# main.net
KiCad netlist of a schematic drawn in EAGLE
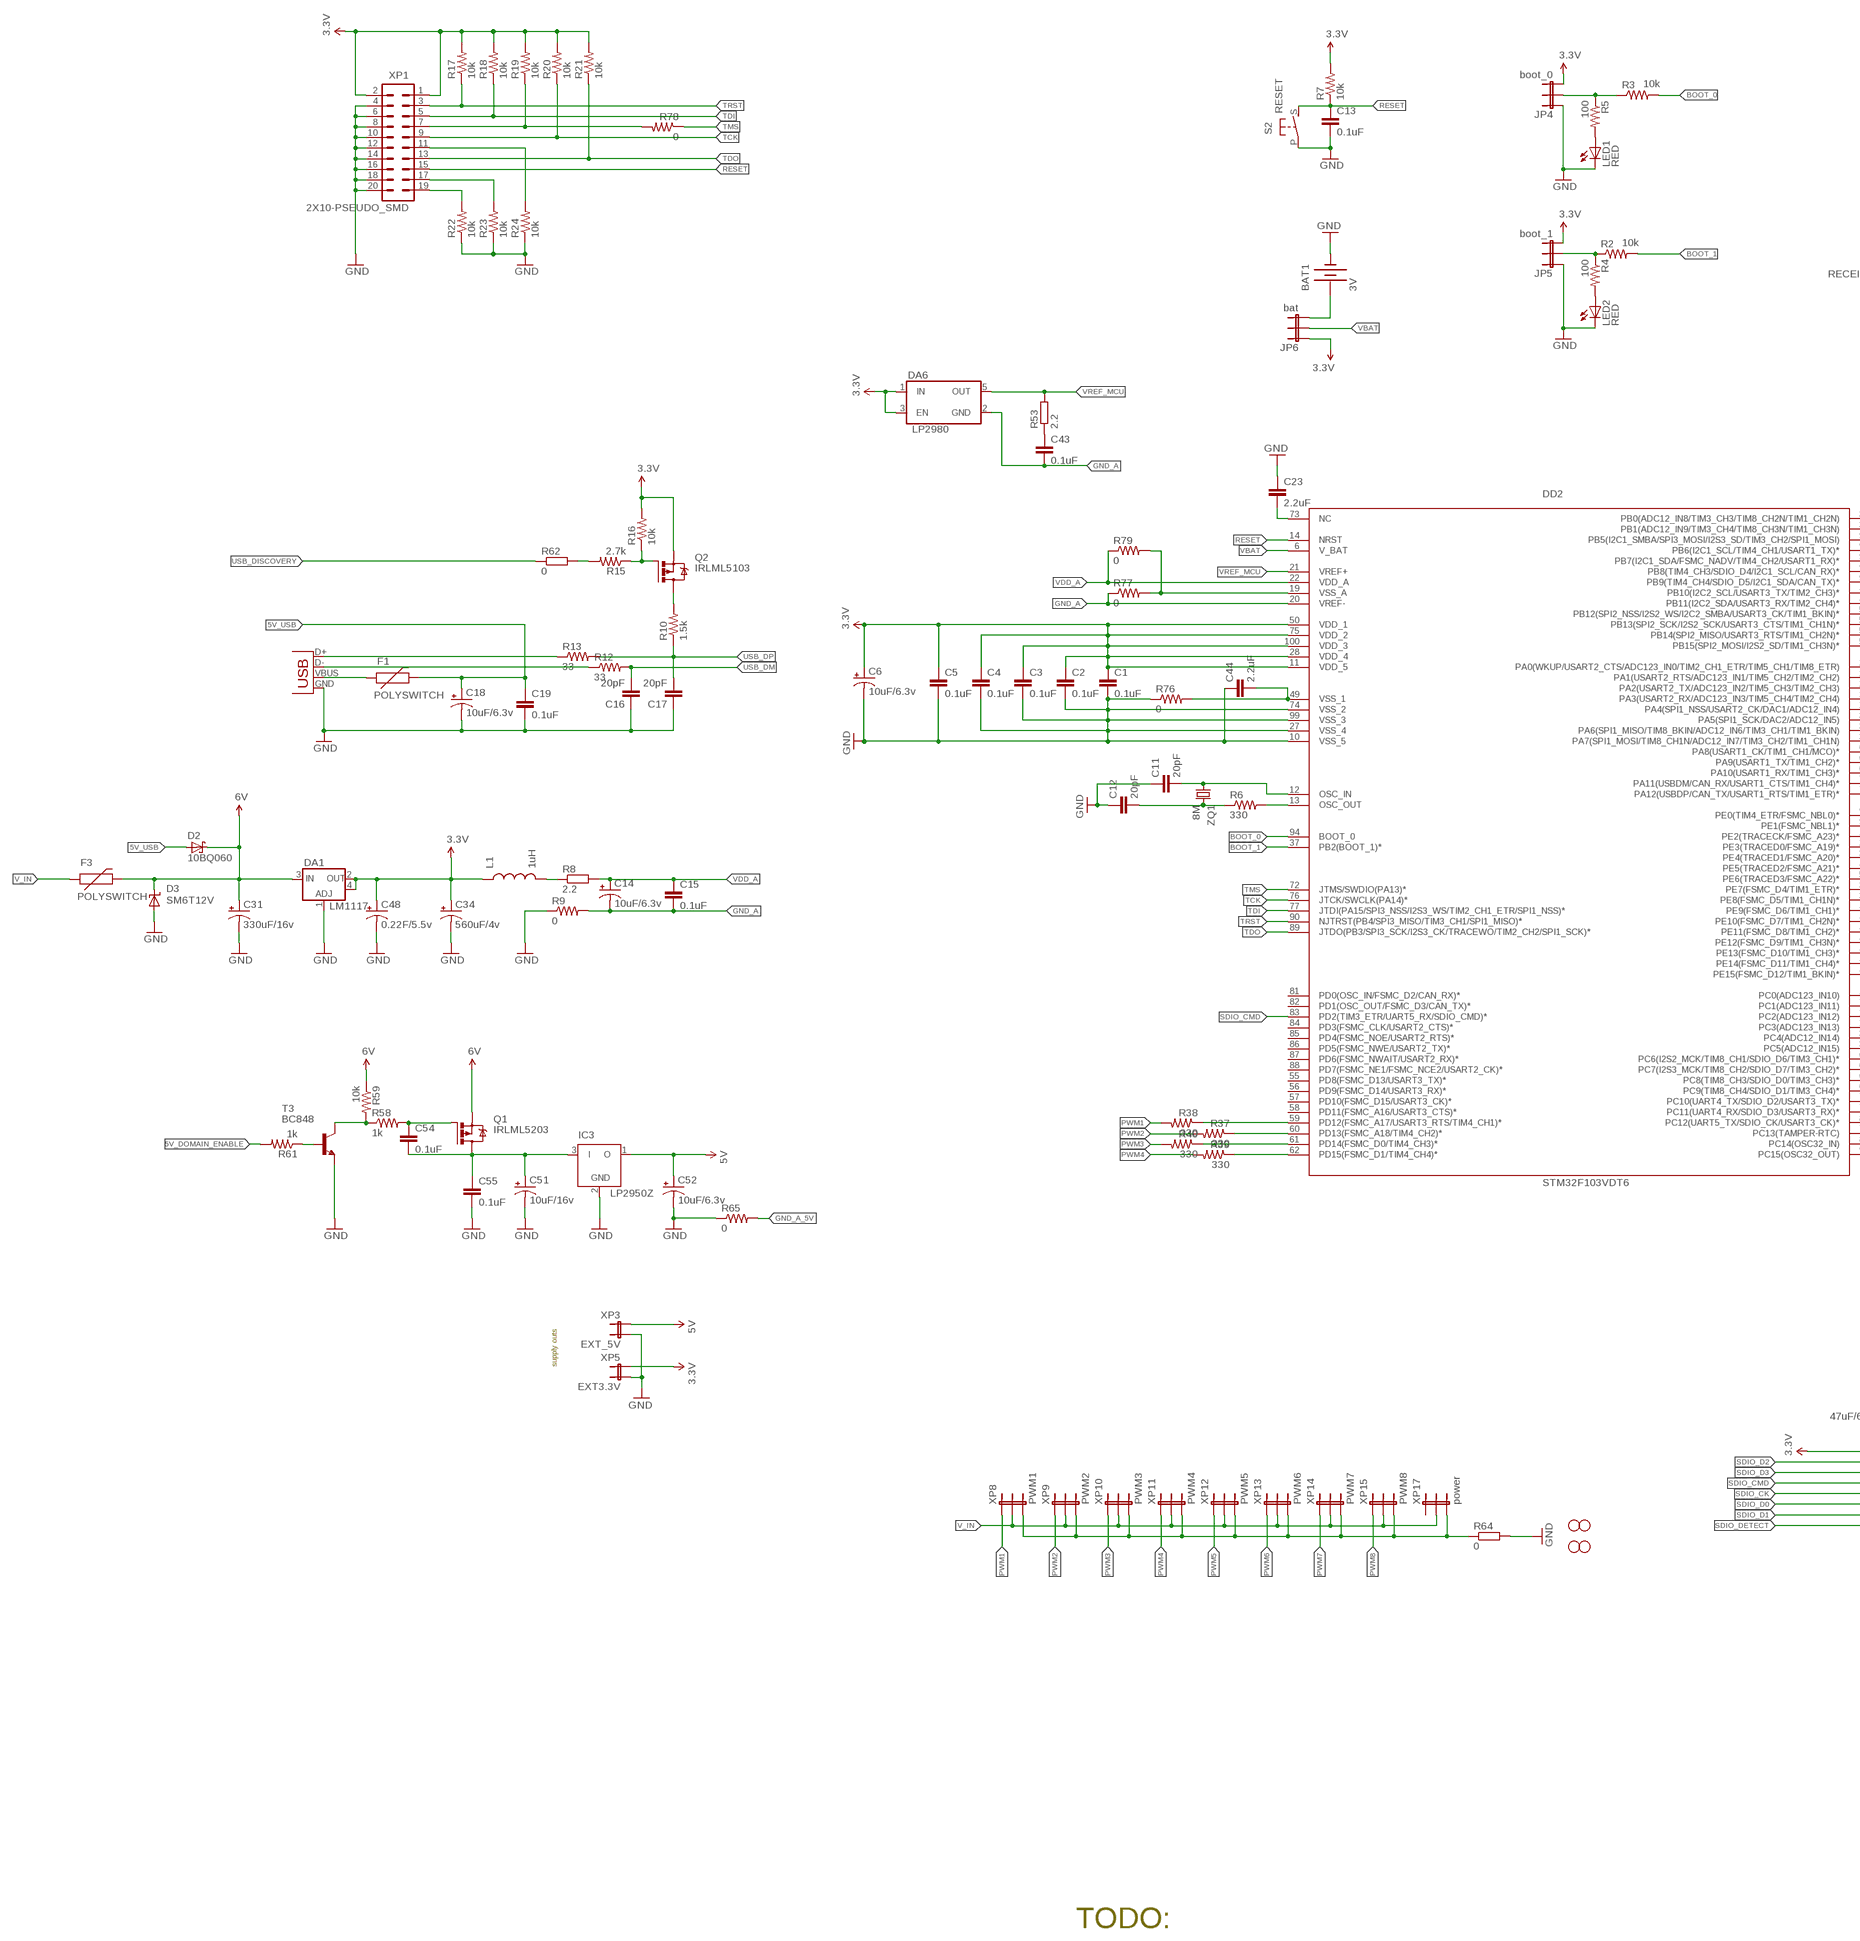
[diagram p0: schematic, sheet 1, part 1 of 3]
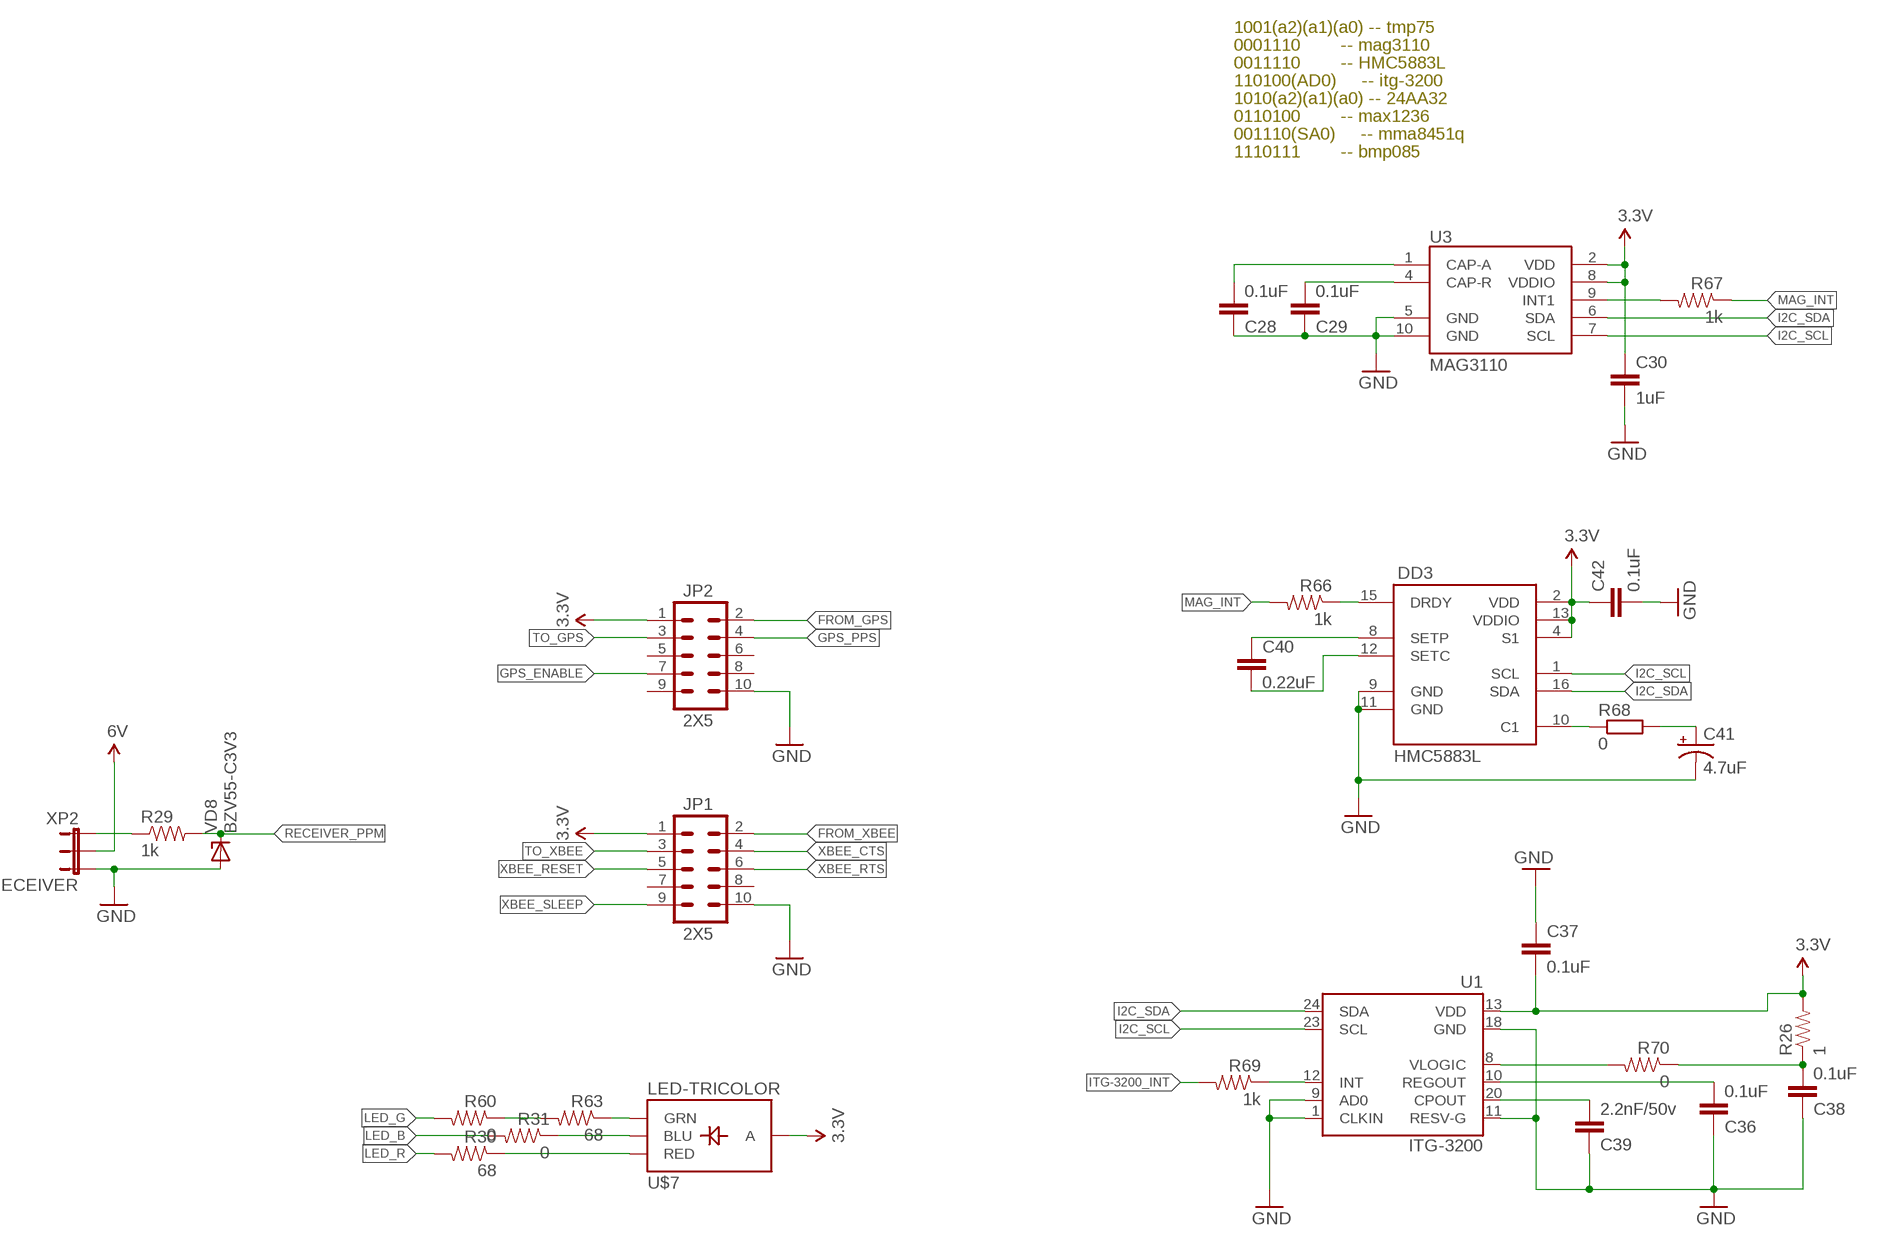
[diagram p1: schematic, sheet 1, part 2 of 3]
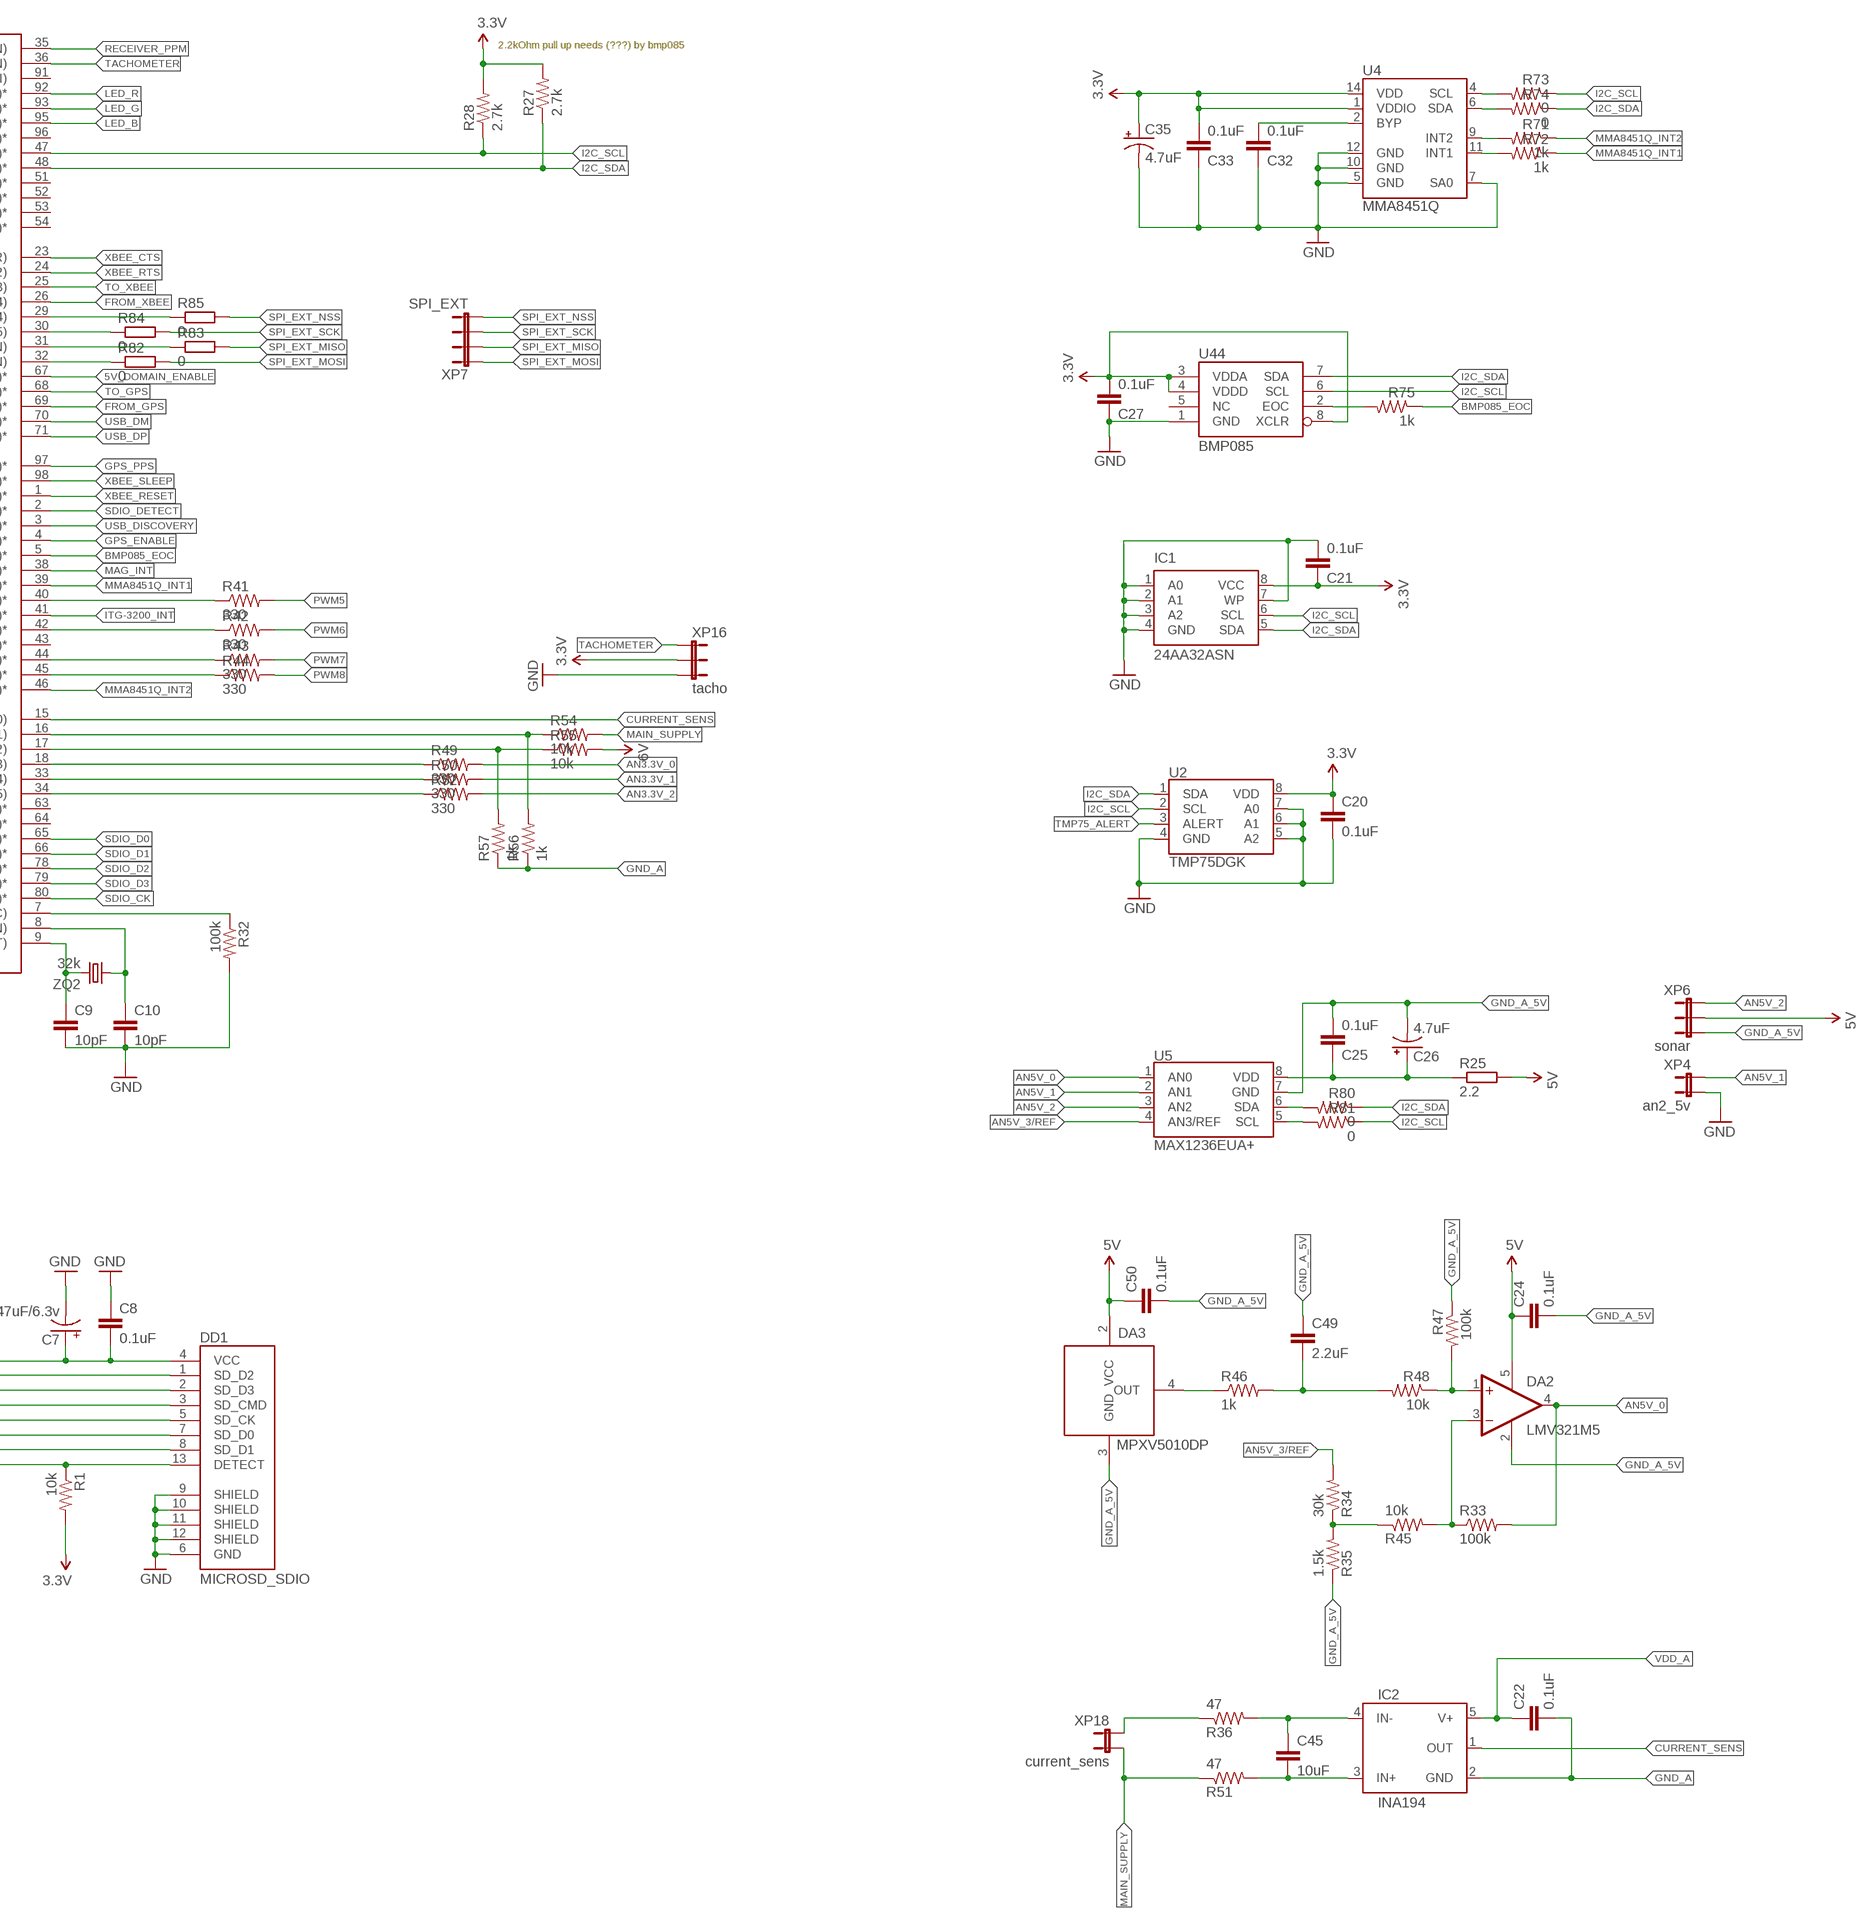
[diagram p2: schematic, sheet 1, part 3 of 3]

(export (version "E")
  (design (tool "Eeschema 10.0.6"))
  (components
    (comp (ref "BAT1")
      (value "3V")
      (footprint "eagle-import:BATTCOM_20MM_PTH")
      (libsource (lib "eagle-import") (part "BATTERY20PTH"))
    )
    (comp (ref "C1")
      (value "0.1uF")
      (footprint "eagle-import:0805")
      (libsource (lib "eagle-import") (part "CAP0805"))
    )
    (comp (ref "C2")
      (value "0.1uF")
      (footprint "eagle-import:0805")
      (libsource (lib "eagle-import") (part "CAP0805"))
    )
    (comp (ref "C3")
      (value "0.1uF")
      (footprint "eagle-import:0805")
      (libsource (lib "eagle-import") (part "CAP0805"))
    )
    (comp (ref "C4")
      (value "0.1uF")
      (footprint "eagle-import:0805")
      (libsource (lib "eagle-import") (part "CAP0805"))
    )
    (comp (ref "C5")
      (value "0.1uF")
      (footprint "eagle-import:0805")
      (libsource (lib "eagle-import") (part "CAP0805"))
    )
    (comp (ref "C6")
      (value "10uF/6.3v")
      (footprint "eagle-import:EIA3216-KIT")
      (libsource (lib "eagle-import") (part "CAP_POL1206-KIT"))
    )
    (comp (ref "C7")
      (value "47uF/6.3v")
      (footprint "eagle-import:EIA3216-KIT")
      (libsource (lib "eagle-import") (part "CAP_POL1206-KIT"))
    )
    (comp (ref "C8")
      (value "0.1uF")
      (footprint "eagle-import:0805")
      (libsource (lib "eagle-import") (part "CAP0805"))
    )
    (comp (ref "C9")
      (value "10pF")
      (footprint "eagle-import:0805")
      (libsource (lib "eagle-import") (part "CAP0805"))
    )
    (comp (ref "C10")
      (value "10pF")
      (footprint "eagle-import:0805")
      (libsource (lib "eagle-import") (part "CAP0805"))
    )
    (comp (ref "C11")
      (value "20pF")
      (footprint "eagle-import:0805")
      (libsource (lib "eagle-import") (part "CAP0805"))
    )
    (comp (ref "C12")
      (value "20pF")
      (footprint "eagle-import:0805")
      (libsource (lib "eagle-import") (part "CAP0805"))
    )
    (comp (ref "C13")
      (value "0.1uF")
      (footprint "eagle-import:0805")
      (libsource (lib "eagle-import") (part "CAP0805"))
    )
    (comp (ref "C14")
      (value "10uF/6.3v")
      (footprint "eagle-import:EIA3216-KIT")
      (libsource (lib "eagle-import") (part "CAP_POL1206-KIT"))
    )
    (comp (ref "C15")
      (value "0.1uF")
      (footprint "eagle-import:0805")
      (libsource (lib "eagle-import") (part "CAP0805"))
    )
    (comp (ref "C16")
      (value "20pF")
      (footprint "eagle-import:0805")
      (libsource (lib "eagle-import") (part "CAP0805"))
    )
    (comp (ref "C17")
      (value "20pF")
      (footprint "eagle-import:0805")
      (libsource (lib "eagle-import") (part "CAP0805"))
    )
    (comp (ref "C18")
      (value "10uF/6.3v")
      (footprint "eagle-import:EIA3216-KIT")
      (libsource (lib "eagle-import") (part "CAP_POL1206-KIT"))
    )
    (comp (ref "C19")
      (value "0.1uF")
      (footprint "eagle-import:0805")
      (libsource (lib "eagle-import") (part "CAP0805"))
    )
    (comp (ref "C20")
      (value "0.1uF")
      (footprint "eagle-import:0805")
      (libsource (lib "eagle-import") (part "CAP0805"))
    )
    (comp (ref "C21")
      (value "0.1uF")
      (footprint "eagle-import:0805")
      (libsource (lib "eagle-import") (part "CAP0805"))
    )
    (comp (ref "C22")
      (value "0.1uF")
      (footprint "eagle-import:0805")
      (libsource (lib "eagle-import") (part "CAP0805"))
    )
    (comp (ref "C23")
      (value "2.2uF")
      (footprint "eagle-import:0805")
      (libsource (lib "eagle-import") (part "CAP0805"))
    )
    (comp (ref "C24")
      (value "0.1uF")
      (footprint "eagle-import:0805")
      (libsource (lib "eagle-import") (part "CAP0805"))
    )
    (comp (ref "C25")
      (value "0.1uF")
      (footprint "eagle-import:0805")
      (libsource (lib "eagle-import") (part "CAP0805"))
    )
    (comp (ref "C26")
      (value "4.7uF")
      (footprint "eagle-import:EIA3216-KIT")
      (libsource (lib "eagle-import") (part "CAP_POL1206-KIT"))
    )
    (comp (ref "C27")
      (value "0.1uF")
      (footprint "eagle-import:0805")
      (libsource (lib "eagle-import") (part "CAP0805"))
    )
    (comp (ref "C28")
      (value "0.1uF")
      (footprint "eagle-import:0805")
      (libsource (lib "eagle-import") (part "CAP0805"))
    )
    (comp (ref "C29")
      (value "0.1uF")
      (footprint "eagle-import:0805")
      (libsource (lib "eagle-import") (part "CAP0805"))
    )
    (comp (ref "C30")
      (value "1uF")
      (footprint "eagle-import:0805")
      (libsource (lib "eagle-import") (part "CAP0805"))
    )
    (comp (ref "C31")
      (value "330uF/16v")
      (footprint "eagle-import:CPOL-RADIAL-1000UF-25V")
      (libsource (lib "eagle-import") (part "CAP_POLPTH4"))
    )
    (comp (ref "C32")
      (value "0.1uF")
      (footprint "eagle-import:0805")
      (libsource (lib "eagle-import") (part "CAP0805"))
    )
    (comp (ref "C33")
      (value "0.1uF")
      (footprint "eagle-import:0805")
      (libsource (lib "eagle-import") (part "CAP0805"))
    )
    (comp (ref "C34")
      (value "560uF/4v")
      (footprint "eagle-import:E3,5-8")
      (libsource (lib "eagle-import") (part "CPOL-USE3.5-8"))
    )
    (comp (ref "C35")
      (value "4.7uF")
      (footprint "eagle-import:EIA3216-KIT")
      (libsource (lib "eagle-import") (part "CAP_POL1206-KIT"))
    )
    (comp (ref "C36")
      (value "0.1uF")
      (footprint "eagle-import:0805")
      (libsource (lib "eagle-import") (part "CAP0805"))
    )
    (comp (ref "C37")
      (value "0.1uF")
      (footprint "eagle-import:0805")
      (libsource (lib "eagle-import") (part "CAP0805"))
    )
    (comp (ref "C38")
      (value "0.1uF")
      (footprint "eagle-import:0805")
      (libsource (lib "eagle-import") (part "CAP0805"))
    )
    (comp (ref "C39")
      (value "2.2nF/50v")
      (footprint "eagle-import:0805")
      (libsource (lib "eagle-import") (part "CAP0805"))
    )
    (comp (ref "C40")
      (value "0.22uF")
      (footprint "eagle-import:0805")
      (libsource (lib "eagle-import") (part "CAP0805"))
    )
    (comp (ref "C41")
      (value "4.7uF")
      (footprint "eagle-import:EIA3216-KIT")
      (libsource (lib "eagle-import") (part "CAP_POL1206-KIT"))
    )
    (comp (ref "C42")
      (value "0.1uF")
      (footprint "eagle-import:0805")
      (libsource (lib "eagle-import") (part "CAP0805"))
    )
    (comp (ref "C43")
      (value "0.1uF")
      (footprint "eagle-import:0805")
      (libsource (lib "eagle-import") (part "CAP0805"))
    )
    (comp (ref "C44")
      (value "2.2uF")
      (footprint "eagle-import:0805")
      (libsource (lib "eagle-import") (part "CAP0805"))
    )
    (comp (ref "C45")
      (value "10uF")
      (footprint "eagle-import:1206")
      (libsource (lib "eagle-import") (part "CAP1206"))
    )
    (comp (ref "C48")
      (value "0.22F/5.5v")
      (footprint "eagle-import:CAP-IONISTOR-5MM")
      (libsource (lib "eagle-import") (part "CAP_POLIONISTOR"))
    )
    (comp (ref "C49")
      (value "2.2uF")
      (footprint "eagle-import:C1206")
      (libsource (lib "eagle-import") (part "C-EUC1206"))
    )
    (comp (ref "C50")
      (value "0.1uF")
      (footprint "eagle-import:0805")
      (libsource (lib "eagle-import") (part "CAP0805"))
    )
    (comp (ref "C51")
      (value "10uF/16v")
      (footprint "eagle-import:EIA3216-KIT")
      (libsource (lib "eagle-import") (part "CAP_POL1206-KIT"))
    )
    (comp (ref "C52")
      (value "10uF/6.3v")
      (footprint "eagle-import:EIA3216-KIT")
      (libsource (lib "eagle-import") (part "CAP_POL1206-KIT"))
    )
    (comp (ref "C54")
      (value "0.1uF")
      (footprint "eagle-import:0805")
      (libsource (lib "eagle-import") (part "CAP0805"))
    )
    (comp (ref "C55")
      (value "0.1uF")
      (footprint "eagle-import:0805")
      (libsource (lib "eagle-import") (part "CAP0805"))
    )
    (comp (ref "D2")
      (value "10BQ060")
      (footprint "eagle-import:SMB")
      (libsource (lib "eagle-import") (part "SCHOTTKY-DIODESMD"))
    )
    (comp (ref "D3")
      (value "SM6T12V")
      (footprint "eagle-import:SMBJ")
      (libsource (lib "eagle-import") (part "SUPPRESSOR-SMBJ"))
    )
    (comp (ref "DA1")
      (value "LM1117")
      (footprint "eagle-import:SOT223")
      (libsource (lib "eagle-import") (part "LM1117"))
    )
    (comp (ref "DA2")
      (value "LMV321M5")
      (footprint "eagle-import:SOT23-5")
      (libsource (lib "eagle-import") (part "LMV321?M5"))
    )
    (comp (ref "DA3")
      (value "MPXV5010DP")
      (footprint "eagle-import:482")
      (libsource (lib "eagle-import") (part "MPXV5010DP"))
    )
    (comp (ref "DA6")
      (value "LP2980")
      (footprint "eagle-import:SOT23-5")
      (libsource (lib "eagle-import") (part "LP2980"))
    )
    (comp (ref "DD1")
      (value "MICROSD_SDIO")
      (footprint "eagle-import:MICROSD")
      (libsource (lib "eagle-import") (part "MICROSD_SDIO"))
    )
    (comp (ref "DD2")
      (value "STM32F103VDT6")
      (footprint "eagle-import:TQFP100")
      (libsource (lib "eagle-import") (part "STM32F103VDT6"))
    )
    (comp (ref "DD3")
      (value "HMC5883L")
      (footprint "eagle-import:16LPCC")
      (libsource (lib "eagle-import") (part "HMC5883L"))
    )
    (comp (ref "F1")
      (value "POLYSWITCH")
      (footprint "eagle-import:1812")
      (libsource (lib "eagle-import") (part "POLYSWITCH"))
    )
    (comp (ref "F3")
      (value "POLYSWITCH")
      (footprint "eagle-import:1812")
      (libsource (lib "eagle-import") (part "POLYSWITCH"))
    )
    (comp (ref "IC1")
      (value "24AA32ASN")
      (footprint "eagle-import:SO-08")
      (fields (field (name "MF") "MICROCHIP") (field (name "MPN") "24AA32A-I/SN"))
      (libsource (lib "eagle-import") (part "24SNAA32A"))
    )
    (comp (ref "IC2")
      (value "INA194")
      (footprint "eagle-import:SOT23-5")
      (fields (field (name "MF") "TEXAS INSTRUMENTS") (field (name "MPN") "INA168NA/250"))
      (libsource (lib "eagle-import") (part "INA194"))
    )
    (comp (ref "IC3")
      (value "LP2950Z")
      (footprint "eagle-import:TO92")
      (libsource (lib "eagle-import") (part "LP2950Z"))
    )
    (comp (ref "JP1")
      (value "2X5")
      (footprint "eagle-import:2X5-PSEUDOSMD")
      (libsource (lib "eagle-import") (part "2X5"))
    )
    (comp (ref "JP2")
      (value "2X5")
      (footprint "eagle-import:2X5-PSEUDOSMD")
      (libsource (lib "eagle-import") (part "2X5"))
    )
    (comp (ref "JP3")
      (value "STAND-OFFTIGHT")
      (footprint "eagle-import:STAND-OFF-TIGHT")
      (libsource (lib "eagle-import") (part "STAND-OFFTIGHT"))
    )
    (comp (ref "JP4")
      (value "boot_0")
      (footprint "eagle-import:1X03")
      (libsource (lib "eagle-import") (part "JUMPER-3PTH"))
    )
    (comp (ref "JP5")
      (value "boot_1")
      (footprint "eagle-import:1X03")
      (libsource (lib "eagle-import") (part "JUMPER-3PTH"))
    )
    (comp (ref "JP6")
      (value "bat")
      (footprint "eagle-import:1X03")
      (libsource (lib "eagle-import") (part "JUMPER-3PTH"))
    )
    (comp (ref "JP7")
      (value "STAND-OFFTIGHT")
      (footprint "eagle-import:STAND-OFF-TIGHT")
      (libsource (lib "eagle-import") (part "STAND-OFFTIGHT"))
    )
    (comp (ref "JP8")
      (value "STAND-OFFTIGHT")
      (footprint "eagle-import:STAND-OFF-TIGHT")
      (libsource (lib "eagle-import") (part "STAND-OFFTIGHT"))
    )
    (comp (ref "JP9")
      (value "STAND-OFFTIGHT")
      (footprint "eagle-import:STAND-OFF-TIGHT")
      (libsource (lib "eagle-import") (part "STAND-OFFTIGHT"))
    )
    (comp (ref "L1")
      (value "1uH")
      (footprint "eagle-import:1210")
      (libsource (lib "eagle-import") (part "INDUCTOR1210"))
    )
    (comp (ref "LED1")
      (value "RED")
      (footprint "eagle-import:LED-0805")
      (libsource (lib "eagle-import") (part "LED0805"))
    )
    (comp (ref "LED2")
      (value "RED")
      (footprint "eagle-import:LED-0805")
      (libsource (lib "eagle-import") (part "LED0805"))
    )
    (comp (ref "Q1")
      (value "IRLML5203")
      (footprint "eagle-import:MICRO3")
      (libsource (lib "eagle-import") (part "IRLML5203"))
    )
    (comp (ref "Q2")
      (value "IRLML5103")
      (footprint "eagle-import:MICRO3")
      (libsource (lib "eagle-import") (part "IRLML5203"))
    )
    (comp (ref "R1")
      (value "10k")
      (footprint "eagle-import:0805")
      (libsource (lib "eagle-import") (part "RESISTOR0805-RES"))
    )
    (comp (ref "R2")
      (value "10k")
      (footprint "eagle-import:0805")
      (libsource (lib "eagle-import") (part "RESISTOR0805-RES"))
    )
    (comp (ref "R3")
      (value "10k")
      (footprint "eagle-import:0805")
      (libsource (lib "eagle-import") (part "RESISTOR0805-RES"))
    )
    (comp (ref "R4")
      (value "100")
      (footprint "eagle-import:0805")
      (libsource (lib "eagle-import") (part "RESISTOR0805-RES"))
    )
    (comp (ref "R5")
      (value "100")
      (footprint "eagle-import:0805")
      (libsource (lib "eagle-import") (part "RESISTOR0805-RES"))
    )
    (comp (ref "R6")
      (value "330")
      (footprint "eagle-import:0805")
      (libsource (lib "eagle-import") (part "RESISTOR0805-RES"))
    )
    (comp (ref "R7")
      (value "10k")
      (footprint "eagle-import:0805")
      (libsource (lib "eagle-import") (part "RESISTOR0805-RES"))
    )
    (comp (ref "R8")
      (value "2.2")
      (footprint "eagle-import:R1206")
      (libsource (lib "eagle-import") (part "R-EU_R1206"))
    )
    (comp (ref "R9")
      (value "0")
      (footprint "eagle-import:0805")
      (libsource (lib "eagle-import") (part "RESISTOR0805-RES"))
    )
    (comp (ref "R10")
      (value "1.5k")
      (footprint "eagle-import:0805")
      (libsource (lib "eagle-import") (part "RESISTOR0805-RES"))
    )
    (comp (ref "R12")
      (value "33")
      (footprint "eagle-import:0805")
      (libsource (lib "eagle-import") (part "RESISTOR0805-RES"))
    )
    (comp (ref "R13")
      (value "33")
      (footprint "eagle-import:0805")
      (libsource (lib "eagle-import") (part "RESISTOR0805-RES"))
    )
    (comp (ref "R15")
      (value "2.7k")
      (footprint "eagle-import:0805")
      (libsource (lib "eagle-import") (part "RESISTOR0805-RES"))
    )
    (comp (ref "R16")
      (value "10k")
      (footprint "eagle-import:0805")
      (libsource (lib "eagle-import") (part "RESISTOR0805-RES"))
    )
    (comp (ref "R17")
      (value "10k")
      (footprint "eagle-import:0805")
      (libsource (lib "eagle-import") (part "RESISTOR0805-RES"))
    )
    (comp (ref "R18")
      (value "10k")
      (footprint "eagle-import:0805")
      (libsource (lib "eagle-import") (part "RESISTOR0805-RES"))
    )
    (comp (ref "R19")
      (value "10k")
      (footprint "eagle-import:0805")
      (libsource (lib "eagle-import") (part "RESISTOR0805-RES"))
    )
    (comp (ref "R20")
      (value "10k")
      (footprint "eagle-import:0805")
      (libsource (lib "eagle-import") (part "RESISTOR0805-RES"))
    )
    (comp (ref "R21")
      (value "10k")
      (footprint "eagle-import:0805")
      (libsource (lib "eagle-import") (part "RESISTOR0805-RES"))
    )
    (comp (ref "R22")
      (value "10k")
      (footprint "eagle-import:0805")
      (libsource (lib "eagle-import") (part "RESISTOR0805-RES"))
    )
    (comp (ref "R23")
      (value "10k")
      (footprint "eagle-import:0805")
      (libsource (lib "eagle-import") (part "RESISTOR0805-RES"))
    )
    (comp (ref "R24")
      (value "10k")
      (footprint "eagle-import:0805")
      (libsource (lib "eagle-import") (part "RESISTOR0805-RES"))
    )
    (comp (ref "R25")
      (value "2.2")
      (footprint "eagle-import:R1206")
      (libsource (lib "eagle-import") (part "barthess_RESISTOR1206"))
    )
    (comp (ref "R26")
      (value "1")
      (footprint "eagle-import:0805")
      (libsource (lib "eagle-import") (part "RESISTOR0805-RES"))
    )
    (comp (ref "R27")
      (value "2.7k")
      (footprint "eagle-import:0805")
      (libsource (lib "eagle-import") (part "RESISTOR0805-RES"))
    )
    (comp (ref "R28")
      (value "2.7k")
      (footprint "eagle-import:0805")
      (libsource (lib "eagle-import") (part "RESISTOR0805-RES"))
    )
    (comp (ref "R29")
      (value "1k")
      (footprint "eagle-import:0805")
      (libsource (lib "eagle-import") (part "RESISTOR0805-RES"))
    )
    (comp (ref "R30")
      (value "68")
      (footprint "eagle-import:0805")
      (libsource (lib "eagle-import") (part "RESISTOR0805-RES"))
    )
    (comp (ref "R31")
      (value "0")
      (footprint "eagle-import:0805")
      (libsource (lib "eagle-import") (part "RESISTOR0805-RES"))
    )
    (comp (ref "R32")
      (value "100k")
      (footprint "eagle-import:0805")
      (libsource (lib "eagle-import") (part "RESISTOR0805-RES"))
    )
    (comp (ref "R33")
      (value "100k")
      (footprint "eagle-import:0805")
      (libsource (lib "eagle-import") (part "RESISTOR0805-RES"))
    )
    (comp (ref "R34")
      (value "30k")
      (footprint "eagle-import:0805")
      (libsource (lib "eagle-import") (part "RESISTOR0805-RES"))
    )
    (comp (ref "R35")
      (value "1.5k")
      (footprint "eagle-import:0805")
      (libsource (lib "eagle-import") (part "RESISTOR0805-RES"))
    )
    (comp (ref "R36")
      (value "47")
      (footprint "eagle-import:0805")
      (libsource (lib "eagle-import") (part "RESISTOR0805-RES"))
    )
    (comp (ref "R37")
      (value "330")
      (footprint "eagle-import:0805")
      (libsource (lib "eagle-import") (part "RESISTOR0805-RES"))
    )
    (comp (ref "R38")
      (value "330")
      (footprint "eagle-import:0805")
      (libsource (lib "eagle-import") (part "RESISTOR0805-RES"))
    )
    (comp (ref "R39")
      (value "330")
      (footprint "eagle-import:0805")
      (libsource (lib "eagle-import") (part "RESISTOR0805-RES"))
    )
    (comp (ref "R40")
      (value "330")
      (footprint "eagle-import:0805")
      (libsource (lib "eagle-import") (part "RESISTOR0805-RES"))
    )
    (comp (ref "R41")
      (value "330")
      (footprint "eagle-import:0805")
      (libsource (lib "eagle-import") (part "RESISTOR0805-RES"))
    )
    (comp (ref "R42")
      (value "330")
      (footprint "eagle-import:0805")
      (libsource (lib "eagle-import") (part "RESISTOR0805-RES"))
    )
    (comp (ref "R43")
      (value "330")
      (footprint "eagle-import:0805")
      (libsource (lib "eagle-import") (part "RESISTOR0805-RES"))
    )
    (comp (ref "R44")
      (value "330")
      (footprint "eagle-import:0805")
      (libsource (lib "eagle-import") (part "RESISTOR0805-RES"))
    )
    (comp (ref "R45")
      (value "10k")
      (footprint "eagle-import:0805")
      (libsource (lib "eagle-import") (part "RESISTOR0805-RES"))
    )
    (comp (ref "R46")
      (value "1k")
      (footprint "eagle-import:0805")
      (libsource (lib "eagle-import") (part "RESISTOR0805-RES"))
    )
    (comp (ref "R47")
      (value "100k")
      (footprint "eagle-import:0805")
      (libsource (lib "eagle-import") (part "RESISTOR0805-RES"))
    )
    (comp (ref "R48")
      (value "10k")
      (footprint "eagle-import:0805")
      (libsource (lib "eagle-import") (part "RESISTOR0805-RES"))
    )
    (comp (ref "R49")
      (value "330")
      (footprint "eagle-import:0805")
      (libsource (lib "eagle-import") (part "RESISTOR0805-RES"))
    )
    (comp (ref "R50")
      (value "330")
      (footprint "eagle-import:0805")
      (libsource (lib "eagle-import") (part "RESISTOR0805-RES"))
    )
    (comp (ref "R51")
      (value "47")
      (footprint "eagle-import:0805")
      (libsource (lib "eagle-import") (part "RESISTOR0805-RES"))
    )
    (comp (ref "R52")
      (value "330")
      (footprint "eagle-import:0805")
      (libsource (lib "eagle-import") (part "RESISTOR0805-RES"))
    )
    (comp (ref "R53")
      (value "2.2")
      (footprint "eagle-import:R1206")
      (libsource (lib "eagle-import") (part "barthess_RESISTOR1206"))
    )
    (comp (ref "R54")
      (value "10k")
      (footprint "eagle-import:0805")
      (libsource (lib "eagle-import") (part "RESISTOR0805-RES"))
    )
    (comp (ref "R55")
      (value "10k")
      (footprint "eagle-import:0805")
      (libsource (lib "eagle-import") (part "RESISTOR0805-RES"))
    )
    (comp (ref "R56")
      (value "1k")
      (footprint "eagle-import:0805")
      (libsource (lib "eagle-import") (part "RESISTOR0805-RES"))
    )
    (comp (ref "R57")
      (value "1k")
      (footprint "eagle-import:0805")
      (libsource (lib "eagle-import") (part "RESISTOR0805-RES"))
    )
    (comp (ref "R58")
      (value "1k")
      (footprint "eagle-import:0805")
      (libsource (lib "eagle-import") (part "RESISTOR0805-RES"))
    )
    (comp (ref "R59")
      (value "10k")
      (footprint "eagle-import:0805")
      (libsource (lib "eagle-import") (part "RESISTOR0805-RES"))
    )
    (comp (ref "R60")
      (value "0")
      (footprint "eagle-import:0805")
      (libsource (lib "eagle-import") (part "RESISTOR0805-RES"))
    )
    (comp (ref "R61")
      (value "1k")
      (footprint "eagle-import:0805")
      (libsource (lib "eagle-import") (part "RESISTOR0805-RES"))
    )
    (comp (ref "R62")
      (value "0")
      (footprint "eagle-import:R1206")
      (libsource (lib "eagle-import") (part "barthess_RESISTOR1206"))
    )
    (comp (ref "R63")
      (value "68")
      (footprint "eagle-import:0805")
      (libsource (lib "eagle-import") (part "RESISTOR0805-RES"))
    )
    (comp (ref "R64")
      (value "0")
      (footprint "eagle-import:R1206")
      (libsource (lib "eagle-import") (part "barthess_RESISTOR1206"))
    )
    (comp (ref "R65")
      (value "0")
      (footprint "eagle-import:0805")
      (libsource (lib "eagle-import") (part "RESISTOR0805-RES"))
    )
    (comp (ref "R66")
      (value "1k")
      (footprint "eagle-import:0805")
      (libsource (lib "eagle-import") (part "RESISTOR0805-RES"))
    )
    (comp (ref "R67")
      (value "1k")
      (footprint "eagle-import:0805")
      (libsource (lib "eagle-import") (part "RESISTOR0805-RES"))
    )
    (comp (ref "R68")
      (value "0")
      (footprint "eagle-import:R1206")
      (libsource (lib "eagle-import") (part "barthess_RESISTOR1206"))
    )
    (comp (ref "R69")
      (value "1k")
      (footprint "eagle-import:0805")
      (libsource (lib "eagle-import") (part "RESISTOR0805-RES"))
    )
    (comp (ref "R70")
      (value "0")
      (footprint "eagle-import:0805")
      (libsource (lib "eagle-import") (part "RESISTOR0805-RES"))
    )
    (comp (ref "R71")
      (value "1k")
      (footprint "eagle-import:0805")
      (libsource (lib "eagle-import") (part "RESISTOR0805-RES"))
    )
    (comp (ref "R72")
      (value "1k")
      (footprint "eagle-import:0805")
      (libsource (lib "eagle-import") (part "RESISTOR0805-RES"))
    )
    (comp (ref "R73")
      (value "0")
      (footprint "eagle-import:0805")
      (libsource (lib "eagle-import") (part "RESISTOR0805-RES"))
    )
    (comp (ref "R74")
      (value "0")
      (footprint "eagle-import:0805")
      (libsource (lib "eagle-import") (part "RESISTOR0805-RES"))
    )
    (comp (ref "R75")
      (value "1k")
      (footprint "eagle-import:0805")
      (libsource (lib "eagle-import") (part "RESISTOR0805-RES"))
    )
    (comp (ref "R76")
      (value "0")
      (footprint "eagle-import:0805")
      (libsource (lib "eagle-import") (part "RESISTOR0805-RES"))
    )
    (comp (ref "R77")
      (value "0")
      (footprint "eagle-import:0805")
      (libsource (lib "eagle-import") (part "RESISTOR0805-RES"))
    )
    (comp (ref "R78")
      (value "0")
      (footprint "eagle-import:0805")
      (libsource (lib "eagle-import") (part "RESISTOR0805-RES"))
    )
    (comp (ref "R79")
      (value "0")
      (footprint "eagle-import:0805")
      (libsource (lib "eagle-import") (part "RESISTOR0805-RES"))
    )
    (comp (ref "R80")
      (value "0")
      (footprint "eagle-import:0805")
      (libsource (lib "eagle-import") (part "RESISTOR0805-RES"))
    )
    (comp (ref "R81")
      (value "0")
      (footprint "eagle-import:0805")
      (libsource (lib "eagle-import") (part "RESISTOR0805-RES"))
    )
    (comp (ref "R82")
      (value "0")
      (footprint "eagle-import:R1206")
      (libsource (lib "eagle-import") (part "barthess_RESISTOR1206"))
    )
    (comp (ref "R83")
      (value "0")
      (footprint "eagle-import:R1206")
      (libsource (lib "eagle-import") (part "barthess_RESISTOR1206"))
    )
    (comp (ref "R84")
      (value "0")
      (footprint "eagle-import:R1206")
      (libsource (lib "eagle-import") (part "barthess_RESISTOR1206"))
    )
    (comp (ref "R85")
      (value "0")
      (footprint "eagle-import:R1206")
      (libsource (lib "eagle-import") (part "barthess_RESISTOR1206"))
    )
    (comp (ref "S2")
      (value "RESET")
      (footprint "eagle-import:BUTTON_6X3.5")
      (libsource (lib "eagle-import") (part "BUTTON_6X3.5"))
    )
    (comp (ref "T3")
      (value "BC848")
      (footprint "eagle-import:SOT23")
      (libsource (lib "eagle-import") (part "BC848"))
    )
    (comp (ref "U$7")
      (value "LED-TRICOLOR")
      (footprint "eagle-import:LED-TRICOLOR-SMD")
      (libsource (lib "eagle-import") (part "LED-TRICOLOR"))
    )
    (comp (ref "U1")
      (value "ITG-3200")
      (footprint "eagle-import:QFN-24")
      (libsource (lib "eagle-import") (part "ITG-3200"))
    )
    (comp (ref "U2")
      (value "TMP75DGK")
      (footprint "eagle-import:MSOP8")
      (libsource (lib "eagle-import") (part "TMP75DGK"))
    )
    (comp (ref "U3")
      (value "MAG3110")
      (footprint "eagle-import:DFN-10")
      (libsource (lib "eagle-import") (part "MAG3110"))
    )
    (comp (ref "U4")
      (value "MMA8451Q")
      (footprint "eagle-import:QFN-16_0.5MM")
      (libsource (lib "eagle-import") (part "MMA8451Q"))
    )
    (comp (ref "U5")
      (value "MAX1236EUA+")
      (footprint "eagle-import:MSOP8")
      (libsource (lib "eagle-import") (part "MAX1236EUA+"))
    )
    (comp (ref "U44")
      (value "BMP085")
      (footprint "eagle-import:BMP085")
      (libsource (lib "eagle-import") (part "BMP085"))
    )
    (comp (ref "VD8")
      (value "BZV55-C3V3")
      (footprint "eagle-import:SOD80C")
      (libsource (lib "eagle-import") (part "BZV55-C3V3"))
    )
    (comp (ref "X1")
      (value "USB-SMD-NS")
      (footprint "eagle-import:USB-MINIB-NOSTOP")
      (libsource (lib "eagle-import") (part "USB-SMD-NS"))
    )
    (comp (ref "XP1")
      (value "2X10-PSEUDO_SMD")
      (footprint "eagle-import:2X10-PSEUDOSMD")
      (libsource (lib "eagle-import") (part "2X10-PSEUDO_SMD"))
    )
    (comp (ref "XP2")
      (value "RECEIVER")
      (footprint "eagle-import:1X03")
      (libsource (lib "eagle-import") (part "JUMPER-3PTH"))
    )
    (comp (ref "XP3")
      (value "EXT_5V")
      (footprint "eagle-import:1X02")
      (libsource (lib "eagle-import") (part "1X2DIP"))
    )
    (comp (ref "XP4")
      (value "an2_5v")
      (footprint "eagle-import:1X02")
      (libsource (lib "eagle-import") (part "1X2DIP"))
    )
    (comp (ref "XP5")
      (value "EXT3.3V")
      (footprint "eagle-import:1X02")
      (libsource (lib "eagle-import") (part "1X2DIP"))
    )
    (comp (ref "XP6")
      (value "sonar")
      (footprint "eagle-import:1X03")
      (libsource (lib "eagle-import") (part "JUMPER-3PTH"))
    )
    (comp (ref "XP7")
      (value "SPI_EXT")
      (footprint "eagle-import:1X4-PSEUDOSMD")
      (libsource (lib "eagle-import") (part "1X4"))
    )
    (comp (ref "XP8")
      (value "PWM1")
      (footprint "eagle-import:1X03")
      (libsource (lib "eagle-import") (part "JUMPER-3PTH"))
    )
    (comp (ref "XP9")
      (value "PWM2")
      (footprint "eagle-import:1X03")
      (libsource (lib "eagle-import") (part "JUMPER-3PTH"))
    )
    (comp (ref "XP10")
      (value "PWM3")
      (footprint "eagle-import:1X03")
      (libsource (lib "eagle-import") (part "JUMPER-3PTH"))
    )
    (comp (ref "XP11")
      (value "PWM4")
      (footprint "eagle-import:1X03")
      (libsource (lib "eagle-import") (part "JUMPER-3PTH"))
    )
    (comp (ref "XP12")
      (value "PWM5")
      (footprint "eagle-import:1X03")
      (libsource (lib "eagle-import") (part "JUMPER-3PTH"))
    )
    (comp (ref "XP13")
      (value "PWM6")
      (footprint "eagle-import:1X03")
      (libsource (lib "eagle-import") (part "JUMPER-3PTH"))
    )
    (comp (ref "XP14")
      (value "PWM7")
      (footprint "eagle-import:1X03")
      (libsource (lib "eagle-import") (part "JUMPER-3PTH"))
    )
    (comp (ref "XP15")
      (value "PWM8")
      (footprint "eagle-import:1X03")
      (libsource (lib "eagle-import") (part "JUMPER-3PTH"))
    )
    (comp (ref "XP16")
      (value "tacho")
      (footprint "eagle-import:1X03")
      (libsource (lib "eagle-import") (part "JUMPER-3PTH"))
    )
    (comp (ref "XP17")
      (value "power")
      (footprint "eagle-import:1X03")
      (libsource (lib "eagle-import") (part "JUMPER-3PTH"))
    )
    (comp (ref "XP18")
      (value "current_sens")
      (footprint "eagle-import:1X02")
      (libsource (lib "eagle-import") (part "1X2DIP"))
    )
    (comp (ref "ZQ1")
      (value "8M")
      (footprint "eagle-import:HC49U-V")
      (libsource (lib "eagle-import") (part "CRYSTALHC49UV"))
    )
    (comp (ref "ZQ2")
      (value "32k")
      (footprint "eagle-import:TC38H")
      (libsource (lib "eagle-import") (part "CRYSTALTC38H"))
    )
  )
  (nets
    (net (code "1") (name "3.3V") (class "Default")
      (node (ref "C1") (pin "1") (pinfunction "1_1") (pintype "passive"))
      (node (ref "C2") (pin "1") (pinfunction "1_1") (pintype "passive"))
      (node (ref "C20") (pin "1") (pinfunction "1_1") (pintype "passive"))
      (node (ref "C21") (pin "1") (pinfunction "1_1") (pintype "passive"))
      (node (ref "C27") (pin "2") (pinfunction "2_2") (pintype "passive"))
      (node (ref "C3") (pin "1") (pinfunction "1_1") (pintype "passive"))
      (node (ref "C30") (pin "1") (pinfunction "1_1") (pintype "passive"))
      (node (ref "C33") (pin "2") (pinfunction "2_2") (pintype "passive"))
      (node (ref "C34") (pin "+") (pinfunction "+_+") (pintype "passive"))
      (node (ref "C35") (pin "A") (pinfunction "+_A") (pintype "passive"))
      (node (ref "C37") (pin "2") (pinfunction "2_2") (pintype "passive"))
      (node (ref "C4") (pin "1") (pinfunction "1_1") (pintype "passive"))
      (node (ref "C42") (pin "1") (pinfunction "1_1") (pintype "passive"))
      (node (ref "C48") (pin "1") (pinfunction "+_1") (pintype "passive"))
      (node (ref "C5") (pin "1") (pinfunction "1_1") (pintype "passive"))
      (node (ref "C6") (pin "A") (pinfunction "+_A") (pintype "passive"))
      (node (ref "C7") (pin "A") (pinfunction "+_A") (pintype "passive"))
      (node (ref "C8") (pin "2") (pinfunction "2_2") (pintype "passive"))
      (node (ref "DA1") (pin "2") (pinfunction "OUT_2") (pintype "power_in"))
      (node (ref "DA1") (pin "4") (pinfunction "OUT_4") (pintype "power_in"))
      (node (ref "DA6") (pin "1") (pinfunction "IN_1") (pintype "power_in"))
      (node (ref "DA6") (pin "3") (pinfunction "EN_3") (pintype "input"))
      (node (ref "DD1") (pin "4") (pinfunction "VCC_4") (pintype "power_in"))
      (node (ref "DD2") (pin "100") (pinfunction "VDD_3_100") (pintype "power_in"))
      (node (ref "DD2") (pin "11") (pinfunction "VDD_5_11") (pintype "power_in"))
      (node (ref "DD2") (pin "28") (pinfunction "VDD_4_28") (pintype "power_in"))
      (node (ref "DD2") (pin "50") (pinfunction "VDD_1_50") (pintype "power_in"))
      (node (ref "DD2") (pin "75") (pinfunction "VDD_2_75") (pintype "power_in"))
      (node (ref "DD3") (pin "13") (pinfunction "VDDIO_13") (pintype "power_in"))
      (node (ref "DD3") (pin "2") (pinfunction "VDD_2") (pintype "power_in"))
      (node (ref "DD3") (pin "4") (pinfunction "S1_4") (pintype "bidirectional"))
      (node (ref "IC1") (pin "8") (pinfunction "VCC_8") (pintype "power_in"))
      (node (ref "JP1") (pin "1") (pinfunction "1_1") (pintype "passive"))
      (node (ref "JP2") (pin "1") (pinfunction "1_1") (pintype "passive"))
      (node (ref "JP4") (pin "3") (pinfunction "3_3") (pintype "passive"))
      (node (ref "JP5") (pin "3") (pinfunction "3_3") (pintype "passive"))
      (node (ref "JP6") (pin "1") (pinfunction "1_1") (pintype "passive"))
      (node (ref "L1") (pin "1") (pinfunction "1_1") (pintype "passive"))
      (node (ref "Q2") (pin "2") (pinfunction "S_2") (pintype "passive"))
      (node (ref "R1") (pin "2") (pinfunction "2_2") (pintype "passive"))
      (node (ref "R16") (pin "2") (pinfunction "2_2") (pintype "passive"))
      (node (ref "R17") (pin "2") (pinfunction "2_2") (pintype "passive"))
      (node (ref "R18") (pin "2") (pinfunction "2_2") (pintype "passive"))
      (node (ref "R19") (pin "2") (pinfunction "2_2") (pintype "passive"))
      (node (ref "R20") (pin "2") (pinfunction "2_2") (pintype "passive"))
      (node (ref "R21") (pin "2") (pinfunction "2_2") (pintype "passive"))
      (node (ref "R26") (pin "2") (pinfunction "2_2") (pintype "passive"))
      (node (ref "R27") (pin "2") (pinfunction "2_2") (pintype "passive"))
      (node (ref "R28") (pin "2") (pinfunction "2_2") (pintype "passive"))
      (node (ref "R7") (pin "2") (pinfunction "2_2") (pintype "passive"))
      (node (ref "U$7") (pin "A") (pinfunction "A_A") (pintype "bidirectional"))
      (node (ref "U1") (pin "13") (pinfunction "VDD_13") (pintype "power_in"))
      (node (ref "U2") (pin "8") (pinfunction "VDD_8") (pintype "power_in"))
      (node (ref "U3") (pin "2") (pinfunction "VDD_2") (pintype "power_in"))
      (node (ref "U3") (pin "8") (pinfunction "VDDIO_8") (pintype "power_in"))
      (node (ref "U4") (pin "1") (pinfunction "VDDIO_1") (pintype "power_in"))
      (node (ref "U4") (pin "14") (pinfunction "VDD_14") (pintype "power_in"))
      (node (ref "U44") (pin "3") (pinfunction "VDDA_3") (pintype "power_in"))
      (node (ref "U44") (pin "4") (pinfunction "VDDD_4") (pintype "power_in"))
      (node (ref "U44") (pin "8") (pinfunction "XCLR_8") (pintype "input"))
      (node (ref "XP1") (pin "1") (pinfunction "1_1") (pintype "passive"))
      (node (ref "XP1") (pin "2") (pinfunction "2_2") (pintype "passive"))
      (node (ref "XP16") (pin "2") (pinfunction "2_2") (pintype "passive"))
      (node (ref "XP5") (pin "1") (pinfunction "1_1") (pintype "passive"))
    )
    (net (code "2") (name "5V") (class "Default")
      (node (ref "C24") (pin "1") (pinfunction "1_1") (pintype "passive"))
      (node (ref "C50") (pin "1") (pinfunction "1_1") (pintype "passive"))
      (node (ref "C52") (pin "A") (pinfunction "+_A") (pintype "passive"))
      (node (ref "DA2") (pin "5") (pinfunction "V+_5") (pintype "power_in"))
      (node (ref "DA3") (pin "2") (pinfunction "VCC_2") (pintype "power_in"))
      (node (ref "IC3") (pin "1") (pinfunction "O_1") (pintype "input"))
      (node (ref "R25") (pin "2") (pinfunction "2_2") (pintype "passive"))
      (node (ref "XP3") (pin "1") (pinfunction "1_1") (pintype "passive"))
      (node (ref "XP6") (pin "2") (pinfunction "2_2") (pintype "passive"))
    )
    (net (code "3") (name "5V_DOMAIN_ENABLE") (class "Default")
      (node (ref "DD2") (pin "67") (pinfunction "PA8(USART1_CK/TIM1_CH1/MCO)*_67") (pintype "bidirectional"))
      (node (ref "R61") (pin "2") (pinfunction "2_2") (pintype "passive"))
    )
    (net (code "4") (name "5V_USB") (class "Default")
      (node (ref "C18") (pin "A") (pinfunction "+_A") (pintype "passive"))
      (node (ref "C19") (pin "1") (pinfunction "1_1") (pintype "passive"))
      (node (ref "D2") (pin "A") (pinfunction "A_A") (pintype "passive"))
      (node (ref "F1") (pin "2") (pinfunction "2_2") (pintype "passive"))
    )
    (net (code "5") (name "6V") (class "Default")
      (node (ref "C31") (pin "1") (pinfunction "+_1") (pintype "passive"))
      (node (ref "D2") (pin "C") (pinfunction "C_C") (pintype "passive"))
      (node (ref "D3") (pin "C") (pinfunction "C_C") (pintype "passive"))
      (node (ref "DA1") (pin "3") (pinfunction "IN_3") (pintype "power_in"))
      (node (ref "F3") (pin "2") (pinfunction "2_2") (pintype "passive"))
      (node (ref "Q1") (pin "2") (pinfunction "S_2") (pintype "passive"))
      (node (ref "R55") (pin "2") (pinfunction "2_2") (pintype "passive"))
      (node (ref "R59") (pin "1") (pinfunction "1_1") (pintype "passive"))
      (node (ref "XP2") (pin "2") (pinfunction "2_2") (pintype "passive"))
    )
    (net (code "6") (name "AN3.3V_0") (class "Default")
      (node (ref "R49") (pin "2") (pinfunction "2_2") (pintype "passive"))
    )
    (net (code "7") (name "AN3.3V_1") (class "Default")
      (node (ref "R50") (pin "2") (pinfunction "2_2") (pintype "passive"))
    )
    (net (code "8") (name "AN3.3V_2") (class "Default")
      (node (ref "R52") (pin "2") (pinfunction "2_2") (pintype "passive"))
    )
    (net (code "9") (name "AN5V_0") (class "Default")
      (node (ref "DA2") (pin "4") (pinfunction "OUT_4") (pintype "output"))
      (node (ref "R33") (pin "2") (pinfunction "2_2") (pintype "passive"))
      (node (ref "U5") (pin "1") (pinfunction "AN0_1") (pintype "input"))
    )
    (net (code "10") (name "AN5V_1") (class "Default")
      (node (ref "U5") (pin "2") (pinfunction "AN1_2") (pintype "input"))
      (node (ref "XP4") (pin "1") (pinfunction "1_1") (pintype "passive"))
    )
    (net (code "11") (name "AN5V_2") (class "Default")
      (node (ref "U5") (pin "3") (pinfunction "AN2_3") (pintype "input"))
      (node (ref "XP6") (pin "1") (pinfunction "1_1") (pintype "passive"))
    )
    (net (code "12") (name "AN5V_3{slash}REF") (class "Default")
      (node (ref "R34") (pin "2") (pinfunction "2_2") (pintype "passive"))
      (node (ref "U5") (pin "4") (pinfunction "AN3/REF_4") (pintype "bidirectional"))
    )
    (net (code "13") (name "BMP085_EOC") (class "Default")
      (node (ref "DD2") (pin "5") (pinfunction "PE6(TRACED3/FSMC_A22)*_5") (pintype "bidirectional"))
      (node (ref "R75") (pin "1") (pinfunction "1_1") (pintype "passive"))
    )
    (net (code "14") (name "BOOT_0") (class "Default")
      (node (ref "DD2") (pin "94") (pinfunction "BOOT_0_94") (pintype "input"))
      (node (ref "R3") (pin "2") (pinfunction "2_2") (pintype "passive"))
    )
    (net (code "15") (name "BOOT_1") (class "Default")
      (node (ref "DD2") (pin "37") (pinfunction "PB2(BOOT_1)*_37") (pintype "bidirectional"))
      (node (ref "R2") (pin "2") (pinfunction "2_2") (pintype "passive"))
    )
    (net (code "16") (name "CURRENT_SENS") (class "Default")
      (node (ref "DD2") (pin "15") (pinfunction "PC0(ADC123_IN10)_15") (pintype "bidirectional"))
      (node (ref "IC2") (pin "1") (pinfunction "OUT_1") (pintype "output"))
    )
    (net (code "17") (name "FROM_GPS") (class "Default")
      (node (ref "DD2") (pin "69") (pinfunction "PA10(USART1_RX/TIM1_CH3)*_69") (pintype "bidirectional"))
      (node (ref "JP2") (pin "2") (pinfunction "2_2") (pintype "passive"))
    )
    (net (code "18") (name "FROM_XBEE") (class "Default")
      (node (ref "DD2") (pin "26") (pinfunction "PA3(USART2_RX/ADC123_IN3/TIM5_CH4/TIM2_CH4)_26") (pintype "bidirectional"))
      (node (ref "JP1") (pin "2") (pinfunction "2_2") (pintype "passive"))
    )
    (net (code "19") (name "GND") (class "Default")
      (node (ref "BAT1") (pin "2") (pinfunction "-_2") (pintype "power_in"))
      (node (ref "C1") (pin "2") (pinfunction "2_2") (pintype "passive"))
      (node (ref "C10") (pin "2") (pinfunction "2_2") (pintype "passive"))
      (node (ref "C11") (pin "1") (pinfunction "1_1") (pintype "passive"))
      (node (ref "C12") (pin "1") (pinfunction "1_1") (pintype "passive"))
      (node (ref "C13") (pin "2") (pinfunction "2_2") (pintype "passive"))
      (node (ref "C16") (pin "1") (pinfunction "1_1") (pintype "passive"))
      (node (ref "C17") (pin "1") (pinfunction "1_1") (pintype "passive"))
      (node (ref "C18") (pin "C") (pinfunction "-_C") (pintype "passive"))
      (node (ref "C19") (pin "2") (pinfunction "2_2") (pintype "passive"))
      (node (ref "C2") (pin "2") (pinfunction "2_2") (pintype "passive"))
      (node (ref "C20") (pin "2") (pinfunction "2_2") (pintype "passive"))
      (node (ref "C21") (pin "2") (pinfunction "2_2") (pintype "passive"))
      (node (ref "C23") (pin "1") (pinfunction "1_1") (pintype "passive"))
      (node (ref "C27") (pin "1") (pinfunction "1_1") (pintype "passive"))
      (node (ref "C28") (pin "1") (pinfunction "1_1") (pintype "passive"))
      (node (ref "C29") (pin "1") (pinfunction "1_1") (pintype "passive"))
      (node (ref "C3") (pin "2") (pinfunction "2_2") (pintype "passive"))
      (node (ref "C30") (pin "2") (pinfunction "2_2") (pintype "passive"))
      (node (ref "C31") (pin "2") (pinfunction "-_2") (pintype "passive"))
      (node (ref "C32") (pin "1") (pinfunction "1_1") (pintype "passive"))
      (node (ref "C33") (pin "1") (pinfunction "1_1") (pintype "passive"))
      (node (ref "C34") (pin "-") (pinfunction "-_-") (pintype "passive"))
      (node (ref "C35") (pin "C") (pinfunction "-_C") (pintype "passive"))
      (node (ref "C36") (pin "1") (pinfunction "1_1") (pintype "passive"))
      (node (ref "C37") (pin "1") (pinfunction "1_1") (pintype "passive"))
      (node (ref "C38") (pin "1") (pinfunction "1_1") (pintype "passive"))
      (node (ref "C39") (pin "1") (pinfunction "1_1") (pintype "passive"))
      (node (ref "C4") (pin "2") (pinfunction "2_2") (pintype "passive"))
      (node (ref "C41") (pin "C") (pinfunction "-_C") (pintype "passive"))
      (node (ref "C42") (pin "2") (pinfunction "2_2") (pintype "passive"))
      (node (ref "C44") (pin "1") (pinfunction "1_1") (pintype "passive"))
      (node (ref "C48") (pin "2") (pinfunction "-_2") (pintype "passive"))
      (node (ref "C5") (pin "2") (pinfunction "2_2") (pintype "passive"))
      (node (ref "C51") (pin "C") (pinfunction "-_C") (pintype "passive"))
      (node (ref "C52") (pin "C") (pinfunction "-_C") (pintype "passive"))
      (node (ref "C55") (pin "2") (pinfunction "2_2") (pintype "passive"))
      (node (ref "C6") (pin "C") (pinfunction "-_C") (pintype "passive"))
      (node (ref "C7") (pin "C") (pinfunction "-_C") (pintype "passive"))
      (node (ref "C8") (pin "1") (pinfunction "1_1") (pintype "passive"))
      (node (ref "C9") (pin "2") (pinfunction "2_2") (pintype "passive"))
      (node (ref "D3") (pin "A") (pinfunction "A_A") (pintype "passive"))
      (node (ref "DA1") (pin "1") (pinfunction "ADJ_1") (pintype "input"))
      (node (ref "DD1") (pin "10") (pinfunction "SHIELD_10") (pintype "power_in"))
      (node (ref "DD1") (pin "11") (pinfunction "SHIELD_11") (pintype "power_in"))
      (node (ref "DD1") (pin "12") (pinfunction "SHIELD_12") (pintype "power_in"))
      (node (ref "DD1") (pin "6") (pinfunction "GND_6") (pintype "power_in"))
      (node (ref "DD1") (pin "9") (pinfunction "SHIELD_9") (pintype "power_in"))
      (node (ref "DD2") (pin "10") (pinfunction "VSS_5_10") (pintype "power_in"))
      (node (ref "DD2") (pin "27") (pinfunction "VSS_4_27") (pintype "power_in"))
      (node (ref "DD2") (pin "74") (pinfunction "VSS_2_74") (pintype "power_in"))
      (node (ref "DD2") (pin "99") (pinfunction "VSS_3_99") (pintype "power_in"))
      (node (ref "DD3") (pin "11") (pinfunction "GND_11") (pintype "power_in"))
      (node (ref "DD3") (pin "9") (pinfunction "GND_9") (pintype "power_in"))
      (node (ref "IC1") (pin "1") (pinfunction "A0_1") (pintype "input"))
      (node (ref "IC1") (pin "2") (pinfunction "A1_2") (pintype "input"))
      (node (ref "IC1") (pin "3") (pinfunction "A2_3") (pintype "input"))
      (node (ref "IC1") (pin "4") (pinfunction "GND_4") (pintype "power_in"))
      (node (ref "IC1") (pin "7") (pinfunction "WP_7") (pintype "input"))
      (node (ref "IC3") (pin "2") (pinfunction "GND_2") (pintype "power_in"))
      (node (ref "JP1") (pin "10") (pinfunction "10_10") (pintype "passive"))
      (node (ref "JP2") (pin "10") (pinfunction "10_10") (pintype "passive"))
      (node (ref "JP4") (pin "1") (pinfunction "1_1") (pintype "passive"))
      (node (ref "JP5") (pin "1") (pinfunction "1_1") (pintype "passive"))
      (node (ref "LED1") (pin "C") (pinfunction "C_C") (pintype "passive"))
      (node (ref "LED2") (pin "C") (pinfunction "C_C") (pintype "passive"))
      (node (ref "R22") (pin "1") (pinfunction "1_1") (pintype "passive"))
      (node (ref "R23") (pin "1") (pinfunction "1_1") (pintype "passive"))
      (node (ref "R24") (pin "1") (pinfunction "1_1") (pintype "passive"))
      (node (ref "R32") (pin "2") (pinfunction "2_2") (pintype "passive"))
      (node (ref "R64") (pin "2") (pinfunction "2_2") (pintype "passive"))
      (node (ref "R65") (pin "1") (pinfunction "1_1") (pintype "passive"))
      (node (ref "R76") (pin "1") (pinfunction "1_1") (pintype "passive"))
      (node (ref "R9") (pin "1") (pinfunction "1_1") (pintype "passive"))
      (node (ref "S2") (pin "P") (pinfunction "P_P") (pintype "passive"))
      (node (ref "T3") (pin "2") (pinfunction "E_2") (pintype "passive"))
      (node (ref "U1") (pin "1") (pinfunction "CLKIN_1") (pintype "input"))
      (node (ref "U1") (pin "11") (pinfunction "RESV-G_11") (pintype "bidirectional"))
      (node (ref "U1") (pin "18") (pinfunction "GND_18") (pintype "power_in"))
      (node (ref "U1") (pin "9") (pinfunction "AD0_9") (pintype "input"))
      (node (ref "U2") (pin "4") (pinfunction "GND_4") (pintype "power_in"))
      (node (ref "U2") (pin "5") (pinfunction "A2_5") (pintype "input"))
      (node (ref "U2") (pin "6") (pinfunction "A1_6") (pintype "input"))
      (node (ref "U2") (pin "7") (pinfunction "A0_7") (pintype "input"))
      (node (ref "U3") (pin "10") (pinfunction "GND_10") (pintype "power_in"))
      (node (ref "U3") (pin "5") (pinfunction "GND_5") (pintype "power_in"))
      (node (ref "U4") (pin "10") (pinfunction "GND_10") (pintype "power_in"))
      (node (ref "U4") (pin "12") (pinfunction "GND_12") (pintype "power_in"))
      (node (ref "U4") (pin "5") (pinfunction "GND_5") (pintype "power_in"))
      (node (ref "U4") (pin "7") (pinfunction "SA0_7") (pintype "input"))
      (node (ref "U44") (pin "1") (pinfunction "GND_1") (pintype "power_in"))
      (node (ref "VD8") (pin "A") (pinfunction "A_A") (pintype "passive"))
      (node (ref "X1") (pin "GND") (pinfunction "GND_GND") (pintype "bidirectional"))
      (node (ref "XP1") (pin "10") (pinfunction "10_10") (pintype "passive"))
      (node (ref "XP1") (pin "12") (pinfunction "12_12") (pintype "passive"))
      (node (ref "XP1") (pin "14") (pinfunction "14_14") (pintype "passive"))
      (node (ref "XP1") (pin "16") (pinfunction "16_16") (pintype "passive"))
      (node (ref "XP1") (pin "18") (pinfunction "18_18") (pintype "passive"))
      (node (ref "XP1") (pin "20") (pinfunction "20_20") (pintype "passive"))
      (node (ref "XP1") (pin "4") (pinfunction "4_4") (pintype "passive"))
      (node (ref "XP1") (pin "6") (pinfunction "6_6") (pintype "passive"))
      (node (ref "XP1") (pin "8") (pinfunction "8_8") (pintype "passive"))
      (node (ref "XP16") (pin "3") (pinfunction "3_3") (pintype "passive"))
      (node (ref "XP2") (pin "3") (pinfunction "3_3") (pintype "passive"))
      (node (ref "XP3") (pin "2") (pinfunction "2_2") (pintype "passive"))
      (node (ref "XP4") (pin "2") (pinfunction "2_2") (pintype "passive"))
      (node (ref "XP5") (pin "2") (pinfunction "2_2") (pintype "passive"))
    )
    (net (code "20") (name "GND_A") (class "Default")
      (node (ref "C14") (pin "C") (pinfunction "-_C") (pintype "passive"))
      (node (ref "C15") (pin "2") (pinfunction "2_2") (pintype "passive"))
      (node (ref "C22") (pin "2") (pinfunction "2_2") (pintype "passive"))
      (node (ref "C43") (pin "2") (pinfunction "2_2") (pintype "passive"))
      (node (ref "DA6") (pin "2") (pinfunction "GND_2") (pintype "input"))
      (node (ref "DD2") (pin "20") (pinfunction "VREF-_20") (pintype "power_in"))
      (node (ref "IC2") (pin "2") (pinfunction "GND_2") (pintype "power_in"))
      (node (ref "R56") (pin "1") (pinfunction "1_1") (pintype "passive"))
      (node (ref "R57") (pin "1") (pinfunction "1_1") (pintype "passive"))
      (node (ref "R77") (pin "1") (pinfunction "1_1") (pintype "passive"))
      (node (ref "R9") (pin "2") (pinfunction "2_2") (pintype "passive"))
    )
    (net (code "21") (name "GND_A_5V") (class "Default")
      (node (ref "C24") (pin "2") (pinfunction "2_2") (pintype "passive"))
      (node (ref "C25") (pin "2") (pinfunction "2_2") (pintype "passive"))
      (node (ref "C26") (pin "C") (pinfunction "-_C") (pintype "passive"))
      (node (ref "C49") (pin "1") (pinfunction "1_1") (pintype "passive"))
      (node (ref "C50") (pin "2") (pinfunction "2_2") (pintype "passive"))
      (node (ref "DA2") (pin "2") (pinfunction "V-_2") (pintype "power_in"))
      (node (ref "DA3") (pin "3") (pinfunction "GND_3") (pintype "power_in"))
      (node (ref "R35") (pin "1") (pinfunction "1_1") (pintype "passive"))
      (node (ref "R47") (pin "1") (pinfunction "1_1") (pintype "passive"))
      (node (ref "R65") (pin "2") (pinfunction "2_2") (pintype "passive"))
      (node (ref "U5") (pin "7") (pinfunction "GND_7") (pintype "power_in"))
      (node (ref "XP6") (pin "3") (pinfunction "3_3") (pintype "passive"))
    )
    (net (code "22") (name "GPS_ENABLE") (class "Default")
      (node (ref "DD2") (pin "4") (pinfunction "PE5(TRACED2/FSMC_A21)*_4") (pintype "bidirectional"))
      (node (ref "JP2") (pin "7") (pinfunction "7_7") (pintype "passive"))
    )
    (net (code "23") (name "GPS_PPS") (class "Default")
      (node (ref "DD2") (pin "97") (pinfunction "PE0(TIM4_ETR/FSMC_NBL0)*_97") (pintype "bidirectional"))
      (node (ref "JP2") (pin "4") (pinfunction "4_4") (pintype "passive"))
    )
    (net (code "24") (name "I2C_SCL") (class "Default")
      (node (ref "DD2") (pin "47") (pinfunction "PB10(I2C2_SCL/USART3_TX/TIM2_CH3)*_47") (pintype "bidirectional"))
      (node (ref "DD3") (pin "1") (pinfunction "SCL_1") (pintype "open_collector"))
      (node (ref "IC1") (pin "6") (pinfunction "SCL_6") (pintype "open_collector"))
      (node (ref "R28") (pin "1") (pinfunction "1_1") (pintype "passive"))
      (node (ref "R73") (pin "1") (pinfunction "1_1") (pintype "passive"))
      (node (ref "R81") (pin "1") (pinfunction "1_1") (pintype "passive"))
      (node (ref "U1") (pin "23") (pinfunction "SCL_23") (pintype "open_collector"))
      (node (ref "U2") (pin "2") (pinfunction "SCL_2") (pintype "open_collector"))
      (node (ref "U3") (pin "7") (pinfunction "SCL_7") (pintype "open_collector"))
      (node (ref "U44") (pin "6") (pinfunction "SCL_6") (pintype "open_collector"))
    )
    (net (code "25") (name "I2C_SDA") (class "Default")
      (node (ref "DD2") (pin "48") (pinfunction "PB11(I2C2_SDA/USART3_RX/TIM2_CH4)*_48") (pintype "bidirectional"))
      (node (ref "DD3") (pin "16") (pinfunction "SDA_16") (pintype "open_collector"))
      (node (ref "IC1") (pin "5") (pinfunction "SDA_5") (pintype "open_collector"))
      (node (ref "R27") (pin "1") (pinfunction "1_1") (pintype "passive"))
      (node (ref "R74") (pin "1") (pinfunction "1_1") (pintype "passive"))
      (node (ref "R80") (pin "1") (pinfunction "1_1") (pintype "passive"))
      (node (ref "U1") (pin "24") (pinfunction "SDA_24") (pintype "open_collector"))
      (node (ref "U2") (pin "1") (pinfunction "SDA_1") (pintype "open_collector"))
      (node (ref "U3") (pin "6") (pinfunction "SDA_6") (pintype "open_collector"))
      (node (ref "U44") (pin "7") (pinfunction "SDA_7") (pintype "open_collector"))
    )
    (net (code "26") (name "ITG-3200_INT") (class "Default")
      (node (ref "DD2") (pin "41") (pinfunction "PE10(FSMC_D7/TIM1_CH2N)*_41") (pintype "bidirectional"))
      (node (ref "R69") (pin "2") (pinfunction "2_2") (pintype "passive"))
    )
    (net (code "27") (name "LED_B") (class "Default")
      (node (ref "DD2") (pin "95") (pinfunction "PB8(TIM4_CH3/SDIO_D4/I2C1_SCL/CAN_RX)*_95") (pintype "bidirectional"))
      (node (ref "R31") (pin "2") (pinfunction "2_2") (pintype "passive"))
    )
    (net (code "28") (name "LED_G") (class "Default")
      (node (ref "DD2") (pin "93") (pinfunction "PB7(I2C1_SDA/FSMC_NADV/TIM4_CH2/USART1_RX)*_93") (pintype "bidirectional"))
      (node (ref "R60") (pin "2") (pinfunction "2_2") (pintype "passive"))
    )
    (net (code "29") (name "LED_R") (class "Default")
      (node (ref "DD2") (pin "92") (pinfunction "PB6(I2C1_SCL/TIM4_CH1/USART1_TX)*_92") (pintype "bidirectional"))
      (node (ref "R30") (pin "2") (pinfunction "2_2") (pintype "passive"))
    )
    (net (code "30") (name "MAG_INT") (class "Default")
      (node (ref "DD2") (pin "38") (pinfunction "PE7(FSMC_D4/TIM1_ETR)*_38") (pintype "bidirectional"))
      (node (ref "R66") (pin "2") (pinfunction "2_2") (pintype "passive"))
      (node (ref "R67") (pin "1") (pinfunction "1_1") (pintype "passive"))
    )
    (net (code "31") (name "MAIN_SUPPLY") (class "Default")
      (node (ref "R51") (pin "1") (pinfunction "1_1") (pintype "passive"))
      (node (ref "R54") (pin "2") (pinfunction "2_2") (pintype "passive"))
      (node (ref "XP18") (pin "2") (pinfunction "2_2") (pintype "passive"))
    )
    (net (code "32") (name "MMA8451Q_INT1") (class "Default")
      (node (ref "DD2") (pin "39") (pinfunction "PE8(FSMC_D5/TIM1_CH1N)*_39") (pintype "bidirectional"))
      (node (ref "R72") (pin "1") (pinfunction "1_1") (pintype "passive"))
    )
    (net (code "33") (name "MMA8451Q_INT2") (class "Default")
      (node (ref "DD2") (pin "46") (pinfunction "PE15(FSMC_D12/TIM1_BKIN)*_46") (pintype "bidirectional"))
      (node (ref "R71") (pin "1") (pinfunction "1_1") (pintype "passive"))
    )
    (net (code "34") (name "Net-(BAT1-+)") (class "Default")
      (node (ref "BAT1") (pin "1") (pinfunction "+_1") (pintype "power_in"))
      (node (ref "JP6") (pin "3") (pinfunction "3_3") (pintype "passive"))
    )
    (net (code "35") (name "Net-(C12-Pad2)") (class "Default")
      (node (ref "C12") (pin "2") (pinfunction "2_2") (pintype "passive"))
      (node (ref "R6") (pin "1") (pinfunction "1_1") (pintype "passive"))
      (node (ref "ZQ1") (pin "2") (pinfunction "2_2") (pintype "passive"))
    )
    (net (code "36") (name "Net-(C26-+)") (class "Default")
      (node (ref "C25") (pin "1") (pinfunction "1_1") (pintype "passive"))
      (node (ref "C26") (pin "A") (pinfunction "+_A") (pintype "passive"))
      (node (ref "R25") (pin "1") (pinfunction "1_1") (pintype "passive"))
      (node (ref "U5") (pin "8") (pinfunction "VDD_8") (pintype "power_in"))
    )
    (net (code "37") (name "Net-(C38-Pad2)") (class "Default")
      (node (ref "C38") (pin "2") (pinfunction "2_2") (pintype "passive"))
      (node (ref "R26") (pin "1") (pinfunction "1_1") (pintype "passive"))
      (node (ref "R70") (pin "1") (pinfunction "1_1") (pintype "passive"))
    )
    (net (code "38") (name "Net-(C41-+)") (class "Default")
      (node (ref "C41") (pin "A") (pinfunction "+_A") (pintype "passive"))
      (node (ref "R68") (pin "2") (pinfunction "2_2") (pintype "passive"))
    )
    (net (code "39") (name "Net-(C43-Pad1)") (class "Default")
      (node (ref "C43") (pin "1") (pinfunction "1_1") (pintype "passive"))
      (node (ref "R53") (pin "1") (pinfunction "1_1") (pintype "passive"))
    )
    (net (code "40") (name "Net-(C49-Pad2)") (class "Default")
      (node (ref "C49") (pin "2") (pinfunction "2_2") (pintype "passive"))
      (node (ref "R46") (pin "2") (pinfunction "2_2") (pintype "passive"))
      (node (ref "R48") (pin "2") (pinfunction "2_2") (pintype "passive"))
    )
    (net (code "41") (name "Net-(C51-+)") (class "Default")
      (node (ref "C51") (pin "A") (pinfunction "+_A") (pintype "passive"))
      (node (ref "C54") (pin "2") (pinfunction "2_2") (pintype "passive"))
      (node (ref "C55") (pin "1") (pinfunction "1_1") (pintype "passive"))
      (node (ref "IC3") (pin "3") (pinfunction "I_3") (pintype "input"))
      (node (ref "Q1") (pin "3") (pinfunction "D_3") (pintype "passive"))
    )
    (net (code "42") (name "Net-(DA2-+IN)") (class "Default")
      (node (ref "DA2") (pin "1") (pinfunction "+IN_1") (pintype "input"))
      (node (ref "R47") (pin "2") (pinfunction "2_2") (pintype "passive"))
      (node (ref "R48") (pin "1") (pinfunction "1_1") (pintype "passive"))
    )
    (net (code "43") (name "Net-(DA2--IN)") (class "Default")
      (node (ref "DA2") (pin "3") (pinfunction "-IN_3") (pintype "input"))
      (node (ref "R33") (pin "1") (pinfunction "1_1") (pintype "passive"))
      (node (ref "R45") (pin "2") (pinfunction "2_2") (pintype "passive"))
    )
    (net (code "44") (name "Net-(DA3-OUT)") (class "Default")
      (node (ref "DA3") (pin "4") (pinfunction "OUT_4") (pintype "output"))
      (node (ref "R46") (pin "1") (pinfunction "1_1") (pintype "passive"))
    )
    (net (code "45") (name "Net-(DD2-NC)") (class "Default")
      (node (ref "C23") (pin "2") (pinfunction "2_2") (pintype "passive"))
      (node (ref "DD2") (pin "73") (pinfunction "NC_73") (pintype "bidirectional"))
    )
    (net (code "46") (name "Net-(DD2-OSC_IN)") (class "Default")
      (node (ref "C11") (pin "2") (pinfunction "2_2") (pintype "passive"))
      (node (ref "DD2") (pin "12") (pinfunction "OSC_IN_12") (pintype "input"))
      (node (ref "ZQ1") (pin "1") (pinfunction "1_1") (pintype "passive"))
    )
    (net (code "47") (name "Net-(DD2-OSC_OUT)") (class "Default")
      (node (ref "DD2") (pin "13") (pinfunction "OSC_OUT_13") (pintype "output"))
      (node (ref "R6") (pin "2") (pinfunction "2_2") (pintype "passive"))
    )
    (net (code "48") (name "Net-(DD2-PA4(SPI1_NSS{slash}USART2_CK{slash}DAC1{slash}ADC12_IN4))") (class "Default")
      (node (ref "DD2") (pin "29") (pinfunction "PA4(SPI1_NSS/USART2_CK/DAC1/ADC12_IN4)_29") (pintype "bidirectional"))
      (node (ref "R85") (pin "1") (pinfunction "1_1") (pintype "passive"))
    )
    (net (code "49") (name "Net-(DD2-PA5(SPI1_SCK{slash}DAC2{slash}ADC12_IN5))") (class "Default")
      (node (ref "DD2") (pin "30") (pinfunction "PA5(SPI1_SCK/DAC2/ADC12_IN5)_30") (pintype "bidirectional"))
      (node (ref "R84") (pin "1") (pinfunction "1_1") (pintype "passive"))
    )
    (net (code "50") (name "Net-(DD2-PA6(SPI1_MISO{slash}TIM8_BKIN{slash}ADC12_IN6{slash}TIM3_CH1{slash}TIM1_BKIN))") (class "Default")
      (node (ref "DD2") (pin "31") (pinfunction "PA6(SPI1_MISO/TIM8_BKIN/ADC12_IN6/TIM3_CH1/TIM1_BKIN)_31") (pintype "bidirectional"))
      (node (ref "R83") (pin "1") (pinfunction "1_1") (pintype "passive"))
    )
    (net (code "51") (name "Net-(DD2-PA7(SPI1_MOSI{slash}TIM8_CH1N{slash}ADC12_IN7{slash}TIM3_CH2{slash}TIM1_CH1N))") (class "Default")
      (node (ref "DD2") (pin "32") (pinfunction "PA7(SPI1_MOSI/TIM8_CH1N/ADC12_IN7/TIM3_CH2/TIM1_CH1N)_32") (pintype "bidirectional"))
      (node (ref "R82") (pin "1") (pinfunction "1_1") (pintype "passive"))
    )
    (net (code "52") (name "Net-(DD2-PC1(ADC123_IN11))") (class "Default")
      (node (ref "DD2") (pin "16") (pinfunction "PC1(ADC123_IN11)_16") (pintype "bidirectional"))
      (node (ref "R54") (pin "1") (pinfunction "1_1") (pintype "passive"))
      (node (ref "R56") (pin "2") (pinfunction "2_2") (pintype "passive"))
    )
    (net (code "53") (name "Net-(DD2-PC2(ADC123_IN12))") (class "Default")
      (node (ref "DD2") (pin "17") (pinfunction "PC2(ADC123_IN12)_17") (pintype "bidirectional"))
      (node (ref "R55") (pin "1") (pinfunction "1_1") (pintype "passive"))
      (node (ref "R57") (pin "2") (pinfunction "2_2") (pintype "passive"))
    )
    (net (code "54") (name "Net-(DD2-PC3(ADC123_IN13))") (class "Default")
      (node (ref "DD2") (pin "18") (pinfunction "PC3(ADC123_IN13)_18") (pintype "bidirectional"))
      (node (ref "R49") (pin "1") (pinfunction "1_1") (pintype "passive"))
    )
    (net (code "55") (name "Net-(DD2-PC4(ADC12_IN14))") (class "Default")
      (node (ref "DD2") (pin "33") (pinfunction "PC4(ADC12_IN14)_33") (pintype "bidirectional"))
      (node (ref "R50") (pin "1") (pinfunction "1_1") (pintype "passive"))
    )
    (net (code "56") (name "Net-(DD2-PC5(ADC12_IN15))") (class "Default")
      (node (ref "DD2") (pin "34") (pinfunction "PC5(ADC12_IN15)_34") (pintype "bidirectional"))
      (node (ref "R52") (pin "1") (pinfunction "1_1") (pintype "passive"))
    )
    (net (code "57") (name "Net-(DD2-PC13(TAMPER-RTC))") (class "Default")
      (node (ref "DD2") (pin "7") (pinfunction "PC13(TAMPER-RTC)_7") (pintype "bidirectional"))
      (node (ref "R32") (pin "1") (pinfunction "1_1") (pintype "passive"))
    )
    (net (code "58") (name "Net-(DD2-PC14(OSC32_IN))") (class "Default")
      (node (ref "C10") (pin "1") (pinfunction "1_1") (pintype "passive"))
      (node (ref "DD2") (pin "8") (pinfunction "PC14(OSC32_IN)_8") (pintype "bidirectional"))
      (node (ref "ZQ2") (pin "1") (pinfunction "1_1") (pintype "passive"))
    )
    (net (code "59") (name "Net-(DD2-PC15(OSC32_OUT))") (class "Default")
      (node (ref "C9") (pin "1") (pinfunction "1_1") (pintype "passive"))
      (node (ref "DD2") (pin "9") (pinfunction "PC15(OSC32_OUT)_9") (pintype "bidirectional"))
      (node (ref "ZQ2") (pin "2") (pinfunction "2_2") (pintype "passive"))
    )
    (net (code "60") (name "Net-(DD2-PD12(FSMC_A17{slash}USART3_RTS{slash}TIM4_CH1)*)") (class "Default")
      (node (ref "DD2") (pin "59") (pinfunction "PD12(FSMC_A17/USART3_RTS/TIM4_CH1)*_59") (pintype "bidirectional"))
      (node (ref "R38") (pin "1") (pinfunction "1_1") (pintype "passive"))
    )
    (net (code "61") (name "Net-(DD2-PD13(FSMC_A18{slash}TIM4_CH2)*)") (class "Default")
      (node (ref "DD2") (pin "60") (pinfunction "PD13(FSMC_A18/TIM4_CH2)*_60") (pintype "bidirectional"))
      (node (ref "R37") (pin "1") (pinfunction "1_1") (pintype "passive"))
    )
    (net (code "62") (name "Net-(DD2-PD14(FSMC_D0{slash}TIM4_CH3)*)") (class "Default")
      (node (ref "DD2") (pin "61") (pinfunction "PD14(FSMC_D0/TIM4_CH3)*_61") (pintype "bidirectional"))
      (node (ref "R40") (pin "1") (pinfunction "1_1") (pintype "passive"))
    )
    (net (code "63") (name "Net-(DD2-PD15(FSMC_D1{slash}TIM4_CH4)*)") (class "Default")
      (node (ref "DD2") (pin "62") (pinfunction "PD15(FSMC_D1/TIM4_CH4)*_62") (pintype "bidirectional"))
      (node (ref "R39") (pin "1") (pinfunction "1_1") (pintype "passive"))
    )
    (net (code "64") (name "Net-(DD2-PE9(FSMC_D6{slash}TIM1_CH1)*)") (class "Default")
      (node (ref "DD2") (pin "40") (pinfunction "PE9(FSMC_D6/TIM1_CH1)*_40") (pintype "bidirectional"))
      (node (ref "R41") (pin "1") (pinfunction "1_1") (pintype "passive"))
    )
    (net (code "65") (name "Net-(DD2-PE11(FSMC_D8{slash}TIM1_CH2)*)") (class "Default")
      (node (ref "DD2") (pin "42") (pinfunction "PE11(FSMC_D8/TIM1_CH2)*_42") (pintype "bidirectional"))
      (node (ref "R42") (pin "1") (pinfunction "1_1") (pintype "passive"))
    )
    (net (code "66") (name "Net-(DD2-PE13(FSMC_D10{slash}TIM1_CH3)*)") (class "Default")
      (node (ref "DD2") (pin "44") (pinfunction "PE13(FSMC_D10/TIM1_CH3)*_44") (pintype "bidirectional"))
      (node (ref "R43") (pin "1") (pinfunction "1_1") (pintype "passive"))
    )
    (net (code "67") (name "Net-(DD2-PE14(FSMC_D11{slash}TIM1_CH4)*)") (class "Default")
      (node (ref "DD2") (pin "45") (pinfunction "PE14(FSMC_D11/TIM1_CH4)*_45") (pintype "bidirectional"))
      (node (ref "R44") (pin "1") (pinfunction "1_1") (pintype "passive"))
    )
    (net (code "68") (name "Net-(DD2-VSS_1)") (class "Default")
      (node (ref "C44") (pin "2") (pinfunction "2_2") (pintype "passive"))
      (node (ref "DD2") (pin "49") (pinfunction "VSS_1_49") (pintype "power_in"))
      (node (ref "R76") (pin "2") (pinfunction "2_2") (pintype "passive"))
    )
    (net (code "69") (name "Net-(DD2-VSS_A)") (class "Default")
      (node (ref "DD2") (pin "19") (pinfunction "VSS_A_19") (pintype "power_in"))
      (node (ref "R77") (pin "2") (pinfunction "2_2") (pintype "passive"))
      (node (ref "R79") (pin "2") (pinfunction "2_2") (pintype "passive"))
    )
    (net (code "70") (name "Net-(DD3-C1)") (class "Default")
      (node (ref "DD3") (pin "10") (pinfunction "C1_10") (pintype "bidirectional"))
      (node (ref "R68") (pin "1") (pinfunction "1_1") (pintype "passive"))
    )
    (net (code "71") (name "Net-(DD3-DRDY)") (class "Default")
      (node (ref "DD3") (pin "15") (pinfunction "DRDY_15") (pintype "output"))
      (node (ref "R66") (pin "1") (pinfunction "1_1") (pintype "passive"))
    )
    (net (code "72") (name "Net-(DD3-SETC)") (class "Default")
      (node (ref "C40") (pin "2") (pinfunction "2_2") (pintype "passive"))
      (node (ref "DD3") (pin "12") (pinfunction "SETC_12") (pintype "bidirectional"))
    )
    (net (code "73") (name "Net-(DD3-SETP)") (class "Default")
      (node (ref "C40") (pin "1") (pinfunction "1_1") (pintype "passive"))
      (node (ref "DD3") (pin "8") (pinfunction "SETP_8") (pintype "bidirectional"))
    )
    (net (code "74") (name "Net-(F1-Pad1)") (class "Default")
      (node (ref "F1") (pin "1") (pinfunction "1_1") (pintype "passive"))
      (node (ref "X1") (pin "VBUS") (pinfunction "VBUS_VBUS") (pintype "bidirectional"))
    )
    (net (code "75") (name "Net-(IC2-IN+)") (class "Default")
      (node (ref "C45") (pin "2") (pinfunction "2_2") (pintype "passive"))
      (node (ref "IC2") (pin "3") (pinfunction "IN+_3") (pintype "input"))
      (node (ref "R51") (pin "2") (pinfunction "2_2") (pintype "passive"))
    )
    (net (code "76") (name "Net-(IC2-IN-)") (class "Default")
      (node (ref "C45") (pin "1") (pinfunction "1_1") (pintype "passive"))
      (node (ref "IC2") (pin "4") (pinfunction "IN-_4") (pintype "input"))
      (node (ref "R36") (pin "2") (pinfunction "2_2") (pintype "passive"))
    )
    (net (code "77") (name "Net-(JP4-Pad2)") (class "Default")
      (node (ref "JP4") (pin "2") (pinfunction "2_2") (pintype "passive"))
      (node (ref "R3") (pin "1") (pinfunction "1_1") (pintype "passive"))
      (node (ref "R5") (pin "1") (pinfunction "1_1") (pintype "passive"))
    )
    (net (code "78") (name "Net-(JP5-Pad2)") (class "Default")
      (node (ref "JP5") (pin "2") (pinfunction "2_2") (pintype "passive"))
      (node (ref "R2") (pin "1") (pinfunction "1_1") (pintype "passive"))
      (node (ref "R4") (pin "1") (pinfunction "1_1") (pintype "passive"))
    )
    (net (code "79") (name "Net-(L1-Pad2)") (class "Default")
      (node (ref "L1") (pin "2") (pinfunction "2_2") (pintype "passive"))
      (node (ref "R8") (pin "1") (pinfunction "1_1") (pintype "passive"))
    )
    (net (code "80") (name "Net-(LED1-PadA)") (class "Default")
      (node (ref "LED1") (pin "A") (pinfunction "A_A") (pintype "passive"))
      (node (ref "R5") (pin "2") (pinfunction "2_2") (pintype "passive"))
    )
    (net (code "81") (name "Net-(LED2-PadA)") (class "Default")
      (node (ref "LED2") (pin "A") (pinfunction "A_A") (pintype "passive"))
      (node (ref "R4") (pin "2") (pinfunction "2_2") (pintype "passive"))
    )
    (net (code "82") (name "Net-(Q1-G)") (class "Default")
      (node (ref "C54") (pin "1") (pinfunction "1_1") (pintype "passive"))
      (node (ref "Q1") (pin "1") (pinfunction "G_1") (pintype "passive"))
      (node (ref "R58") (pin "2") (pinfunction "2_2") (pintype "passive"))
    )
    (net (code "83") (name "Net-(Q2-D)") (class "Default")
      (node (ref "Q2") (pin "3") (pinfunction "D_3") (pintype "passive"))
      (node (ref "R10") (pin "2") (pinfunction "2_2") (pintype "passive"))
    )
    (net (code "84") (name "Net-(Q2-G)") (class "Default")
      (node (ref "Q2") (pin "1") (pinfunction "G_1") (pintype "passive"))
      (node (ref "R15") (pin "1") (pinfunction "1_1") (pintype "passive"))
      (node (ref "R16") (pin "1") (pinfunction "1_1") (pintype "passive"))
    )
    (net (code "85") (name "Net-(R12-Pad1)") (class "Default")
      (node (ref "R12") (pin "1") (pinfunction "1_1") (pintype "passive"))
      (node (ref "X1") (pin "D-") (pinfunction "D-_D-") (pintype "bidirectional"))
    )
    (net (code "86") (name "Net-(R13-Pad1)") (class "Default")
      (node (ref "R13") (pin "1") (pinfunction "1_1") (pintype "passive"))
      (node (ref "X1") (pin "D+") (pinfunction "D+_D+") (pintype "bidirectional"))
    )
    (net (code "87") (name "Net-(R15-Pad2)") (class "Default")
      (node (ref "R15") (pin "2") (pinfunction "2_2") (pintype "passive"))
      (node (ref "R62") (pin "2") (pinfunction "2_2") (pintype "passive"))
    )
    (net (code "88") (name "Net-(R19-Pad1)") (class "Default")
      (node (ref "R19") (pin "1") (pinfunction "1_1") (pintype "passive"))
      (node (ref "R78") (pin "2") (pinfunction "2_2") (pintype "passive"))
      (node (ref "XP1") (pin "7") (pinfunction "7_7") (pintype "passive"))
    )
    (net (code "89") (name "Net-(R22-Pad2)") (class "Default")
      (node (ref "R22") (pin "2") (pinfunction "2_2") (pintype "passive"))
      (node (ref "XP1") (pin "19") (pinfunction "19_19") (pintype "passive"))
    )
    (net (code "90") (name "Net-(R23-Pad2)") (class "Default")
      (node (ref "R23") (pin "2") (pinfunction "2_2") (pintype "passive"))
      (node (ref "XP1") (pin "17") (pinfunction "17_17") (pintype "passive"))
    )
    (net (code "91") (name "Net-(R24-Pad2)") (class "Default")
      (node (ref "R24") (pin "2") (pinfunction "2_2") (pintype "passive"))
      (node (ref "XP1") (pin "11") (pinfunction "11_11") (pintype "passive"))
    )
    (net (code "92") (name "Net-(R29-Pad1)") (class "Default")
      (node (ref "R29") (pin "1") (pinfunction "1_1") (pintype "passive"))
      (node (ref "XP2") (pin "1") (pinfunction "1_1") (pintype "passive"))
    )
    (net (code "93") (name "Net-(R34-Pad1)") (class "Default")
      (node (ref "R34") (pin "1") (pinfunction "1_1") (pintype "passive"))
      (node (ref "R35") (pin "2") (pinfunction "2_2") (pintype "passive"))
      (node (ref "R45") (pin "1") (pinfunction "1_1") (pintype "passive"))
    )
    (net (code "94") (name "Net-(R36-Pad1)") (class "Default")
      (node (ref "R36") (pin "1") (pinfunction "1_1") (pintype "passive"))
      (node (ref "XP18") (pin "1") (pinfunction "1_1") (pintype "passive"))
    )
    (net (code "95") (name "Net-(R60-Pad1)") (class "Default")
      (node (ref "R60") (pin "1") (pinfunction "1_1") (pintype "passive"))
      (node (ref "R63") (pin "2") (pinfunction "2_2") (pintype "passive"))
    )
    (net (code "96") (name "Net-(R64-Pad1)") (class "Default")
      (node (ref "R64") (pin "1") (pinfunction "1_1") (pintype "passive"))
      (node (ref "XP10") (pin "3") (pinfunction "3_3") (pintype "passive"))
      (node (ref "XP11") (pin "3") (pinfunction "3_3") (pintype "passive"))
      (node (ref "XP12") (pin "3") (pinfunction "3_3") (pintype "passive"))
      (node (ref "XP13") (pin "3") (pinfunction "3_3") (pintype "passive"))
      (node (ref "XP14") (pin "3") (pinfunction "3_3") (pintype "passive"))
      (node (ref "XP15") (pin "3") (pinfunction "3_3") (pintype "passive"))
      (node (ref "XP17") (pin "3") (pinfunction "3_3") (pintype "passive"))
      (node (ref "XP8") (pin "3") (pinfunction "3_3") (pintype "passive"))
      (node (ref "XP9") (pin "3") (pinfunction "3_3") (pintype "passive"))
    )
    (net (code "97") (name "Net-(T3-B)") (class "Default")
      (node (ref "R61") (pin "1") (pinfunction "1_1") (pintype "passive"))
      (node (ref "T3") (pin "1") (pinfunction "B_1") (pintype "passive"))
    )
    (net (code "98") (name "Net-(T3-C)") (class "Default")
      (node (ref "R58") (pin "1") (pinfunction "1_1") (pintype "passive"))
      (node (ref "R59") (pin "2") (pinfunction "2_2") (pintype "passive"))
      (node (ref "T3") (pin "3") (pinfunction "C_3") (pintype "passive"))
    )
    (net (code "99") (name "Net-(U$7-BLU)") (class "Default")
      (node (ref "R31") (pin "1") (pinfunction "1_1") (pintype "passive"))
      (node (ref "U$7") (pin "B") (pinfunction "BLU_B") (pintype "bidirectional"))
    )
    (net (code "100") (name "Net-(U$7-GRN)") (class "Default")
      (node (ref "R63") (pin "1") (pinfunction "1_1") (pintype "passive"))
      (node (ref "U$7") (pin "G") (pinfunction "GRN_G") (pintype "bidirectional"))
    )
    (net (code "101") (name "Net-(U$7-RED)") (class "Default")
      (node (ref "R30") (pin "1") (pinfunction "1_1") (pintype "passive"))
      (node (ref "U$7") (pin "R") (pinfunction "RED_R") (pintype "bidirectional"))
    )
    (net (code "102") (name "Net-(U1-CPOUT)") (class "Default")
      (node (ref "C39") (pin "2") (pinfunction "2_2") (pintype "passive"))
      (node (ref "U1") (pin "20") (pinfunction "CPOUT_20") (pintype "output"))
    )
    (net (code "103") (name "Net-(U1-INT)") (class "Default")
      (node (ref "R69") (pin "1") (pinfunction "1_1") (pintype "passive"))
      (node (ref "U1") (pin "12") (pinfunction "INT_12") (pintype "output"))
    )
    (net (code "104") (name "Net-(U1-REGOUT)") (class "Default")
      (node (ref "C36") (pin "2") (pinfunction "2_2") (pintype "passive"))
      (node (ref "U1") (pin "10") (pinfunction "REGOUT_10") (pintype "output"))
    )
    (net (code "105") (name "Net-(U1-VLOGIC)") (class "Default")
      (node (ref "R70") (pin "2") (pinfunction "2_2") (pintype "passive"))
      (node (ref "U1") (pin "8") (pinfunction "VLOGIC_8") (pintype "power_in"))
    )
    (net (code "106") (name "Net-(U3-CAP-A)") (class "Default")
      (node (ref "C28") (pin "2") (pinfunction "2_2") (pintype "passive"))
      (node (ref "U3") (pin "1") (pinfunction "CAP-A_1") (pintype "input"))
    )
    (net (code "107") (name "Net-(U3-CAP-R)") (class "Default")
      (node (ref "C29") (pin "2") (pinfunction "2_2") (pintype "passive"))
      (node (ref "U3") (pin "4") (pinfunction "CAP-R_4") (pintype "input"))
    )
    (net (code "108") (name "Net-(U3-INT1)") (class "Default")
      (node (ref "R67") (pin "2") (pinfunction "2_2") (pintype "passive"))
      (node (ref "U3") (pin "9") (pinfunction "INT1_9") (pintype "output"))
    )
    (net (code "109") (name "Net-(U4-BYP)") (class "Default")
      (node (ref "C32") (pin "2") (pinfunction "2_2") (pintype "passive"))
      (node (ref "U4") (pin "2") (pinfunction "BYP_2") (pintype "input"))
    )
    (net (code "110") (name "Net-(U4-INT1)") (class "Default")
      (node (ref "R72") (pin "2") (pinfunction "2_2") (pintype "passive"))
      (node (ref "U4") (pin "11") (pinfunction "INT1_11") (pintype "output"))
    )
    (net (code "111") (name "Net-(U4-INT2)") (class "Default")
      (node (ref "R71") (pin "2") (pinfunction "2_2") (pintype "passive"))
      (node (ref "U4") (pin "9") (pinfunction "INT2_9") (pintype "output"))
    )
    (net (code "112") (name "Net-(U4-SCL)") (class "Default")
      (node (ref "R73") (pin "2") (pinfunction "2_2") (pintype "passive"))
      (node (ref "U4") (pin "4") (pinfunction "SCL_4") (pintype "open_collector"))
    )
    (net (code "113") (name "Net-(U4-SDA)") (class "Default")
      (node (ref "R74") (pin "2") (pinfunction "2_2") (pintype "passive"))
      (node (ref "U4") (pin "6") (pinfunction "SDA_6") (pintype "open_collector"))
    )
    (net (code "114") (name "Net-(U5-SCL)") (class "Default")
      (node (ref "R81") (pin "2") (pinfunction "2_2") (pintype "passive"))
      (node (ref "U5") (pin "5") (pinfunction "SCL_5") (pintype "open_collector"))
    )
    (net (code "115") (name "Net-(U5-SDA)") (class "Default")
      (node (ref "R80") (pin "2") (pinfunction "2_2") (pintype "passive"))
      (node (ref "U5") (pin "6") (pinfunction "SDA_6") (pintype "open_collector"))
    )
    (net (code "116") (name "Net-(U44-EOC)") (class "Default")
      (node (ref "R75") (pin "2") (pinfunction "2_2") (pintype "passive"))
      (node (ref "U44") (pin "2") (pinfunction "EOC_2") (pintype "output"))
    )
    (net (code "117") (name "PWM1") (class "Default")
      (node (ref "R38") (pin "2") (pinfunction "2_2") (pintype "passive"))
      (node (ref "XP8") (pin "1") (pinfunction "1_1") (pintype "passive"))
    )
    (net (code "118") (name "PWM2") (class "Default")
      (node (ref "R37") (pin "2") (pinfunction "2_2") (pintype "passive"))
      (node (ref "XP9") (pin "1") (pinfunction "1_1") (pintype "passive"))
    )
    (net (code "119") (name "PWM3") (class "Default")
      (node (ref "R40") (pin "2") (pinfunction "2_2") (pintype "passive"))
      (node (ref "XP10") (pin "1") (pinfunction "1_1") (pintype "passive"))
    )
    (net (code "120") (name "PWM4") (class "Default")
      (node (ref "R39") (pin "2") (pinfunction "2_2") (pintype "passive"))
      (node (ref "XP11") (pin "1") (pinfunction "1_1") (pintype "passive"))
    )
    (net (code "121") (name "PWM5") (class "Default")
      (node (ref "R41") (pin "2") (pinfunction "2_2") (pintype "passive"))
      (node (ref "XP12") (pin "1") (pinfunction "1_1") (pintype "passive"))
    )
    (net (code "122") (name "PWM6") (class "Default")
      (node (ref "R42") (pin "2") (pinfunction "2_2") (pintype "passive"))
      (node (ref "XP13") (pin "1") (pinfunction "1_1") (pintype "passive"))
    )
    (net (code "123") (name "PWM7") (class "Default")
      (node (ref "R43") (pin "2") (pinfunction "2_2") (pintype "passive"))
      (node (ref "XP14") (pin "1") (pinfunction "1_1") (pintype "passive"))
    )
    (net (code "124") (name "PWM8") (class "Default")
      (node (ref "R44") (pin "2") (pinfunction "2_2") (pintype "passive"))
      (node (ref "XP15") (pin "1") (pinfunction "1_1") (pintype "passive"))
    )
    (net (code "125") (name "RECEIVER_PPM") (class "Default")
      (node (ref "DD2") (pin "35") (pinfunction "PB0(ADC12_IN8/TIM3_CH3/TIM8_CH2N/TIM1_CH2N)_35") (pintype "bidirectional"))
      (node (ref "R29") (pin "2") (pinfunction "2_2") (pintype "passive"))
      (node (ref "VD8") (pin "C") (pinfunction "C_C") (pintype "passive"))
    )
    (net (code "126") (name "RESET") (class "Default")
      (node (ref "C13") (pin "1") (pinfunction "1_1") (pintype "passive"))
      (node (ref "DD2") (pin "14") (pinfunction "NRST_14") (pintype "bidirectional"))
      (node (ref "R7") (pin "1") (pinfunction "1_1") (pintype "passive"))
      (node (ref "S2") (pin "S") (pinfunction "S_S") (pintype "passive"))
      (node (ref "XP1") (pin "15") (pinfunction "15_15") (pintype "passive"))
    )
    (net (code "127") (name "SDIO_CK") (class "Default")
      (node (ref "DD1") (pin "5") (pinfunction "SD_CK_5") (pintype "input"))
      (node (ref "DD2") (pin "80") (pinfunction "PC12(UART5_TX/SDIO_CK/USART3_CK)*_80") (pintype "bidirectional"))
    )
    (net (code "128") (name "SDIO_CMD") (class "Default")
      (node (ref "DD1") (pin "3") (pinfunction "SD_CMD_3") (pintype "bidirectional"))
      (node (ref "DD2") (pin "83") (pinfunction "PD2(TIM3_ETR/UART5_RX/SDIO_CMD)*_83") (pintype "bidirectional"))
    )
    (net (code "129") (name "SDIO_D0") (class "Default")
      (node (ref "DD1") (pin "7") (pinfunction "SD_D0_7") (pintype "bidirectional"))
      (node (ref "DD2") (pin "65") (pinfunction "PC8(TIM8_CH3/SDIO_D0/TIM3_CH3)*_65") (pintype "bidirectional"))
    )
    (net (code "130") (name "SDIO_D1") (class "Default")
      (node (ref "DD1") (pin "8") (pinfunction "SD_D1_8") (pintype "bidirectional"))
      (node (ref "DD2") (pin "66") (pinfunction "PC9(TIM8_CH4/SDIO_D1/TIM3_CH4)*_66") (pintype "bidirectional"))
    )
    (net (code "131") (name "SDIO_D2") (class "Default")
      (node (ref "DD1") (pin "1") (pinfunction "SD_D2_1") (pintype "bidirectional"))
      (node (ref "DD2") (pin "78") (pinfunction "PC10(UART4_TX/SDIO_D2/USART3_TX)*_78") (pintype "bidirectional"))
    )
    (net (code "132") (name "SDIO_D3") (class "Default")
      (node (ref "DD1") (pin "2") (pinfunction "SD_D3_2") (pintype "bidirectional"))
      (node (ref "DD2") (pin "79") (pinfunction "PC11(UART4_RX/SDIO_D3/USART3_RX)*_79") (pintype "bidirectional"))
    )
    (net (code "133") (name "SDIO_DETECT") (class "Default")
      (node (ref "DD1") (pin "13") (pinfunction "DETECT_13") (pintype "output"))
      (node (ref "DD2") (pin "2") (pinfunction "PE3(TRACED0/FSMC_A19)*_2") (pintype "bidirectional"))
      (node (ref "R1") (pin "1") (pinfunction "1_1") (pintype "passive"))
    )
    (net (code "134") (name "SPI_EXT_MISO") (class "Default")
      (node (ref "R83") (pin "2") (pinfunction "2_2") (pintype "passive"))
      (node (ref "XP7") (pin "2") (pinfunction "2_2") (pintype "passive"))
    )
    (net (code "135") (name "SPI_EXT_MOSI") (class "Default")
      (node (ref "R82") (pin "2") (pinfunction "2_2") (pintype "passive"))
      (node (ref "XP7") (pin "1") (pinfunction "1_1") (pintype "passive"))
    )
    (net (code "136") (name "SPI_EXT_NSS") (class "Default")
      (node (ref "R85") (pin "2") (pinfunction "2_2") (pintype "passive"))
      (node (ref "XP7") (pin "4") (pinfunction "4_4") (pintype "passive"))
    )
    (net (code "137") (name "SPI_EXT_SCK") (class "Default")
      (node (ref "R84") (pin "2") (pinfunction "2_2") (pintype "passive"))
      (node (ref "XP7") (pin "3") (pinfunction "3_3") (pintype "passive"))
    )
    (net (code "138") (name "TACHOMETER") (class "Default")
      (node (ref "DD2") (pin "36") (pinfunction "PB1(ADC12_IN9/TIM3_CH4/TIM8_CH3N/TIM1_CH3N)_36") (pintype "bidirectional"))
      (node (ref "XP16") (pin "1") (pinfunction "1_1") (pintype "passive"))
    )
    (net (code "139") (name "TCK") (class "Default")
      (node (ref "DD2") (pin "76") (pinfunction "JTCK/SWCLK(PA14)*_76") (pintype "bidirectional"))
      (node (ref "R20") (pin "1") (pinfunction "1_1") (pintype "passive"))
      (node (ref "XP1") (pin "9") (pinfunction "9_9") (pintype "passive"))
    )
    (net (code "140") (name "TDI") (class "Default")
      (node (ref "DD2") (pin "77") (pinfunction "JTDI(PA15/SPI3_NSS/I2S3_WS/TIM2_CH1_ETR/SPI1_NSS)*_77") (pintype "bidirectional"))
      (node (ref "R18") (pin "1") (pinfunction "1_1") (pintype "passive"))
      (node (ref "XP1") (pin "5") (pinfunction "5_5") (pintype "passive"))
    )
    (net (code "141") (name "TDO") (class "Default")
      (node (ref "DD2") (pin "89") (pinfunction "JTDO(PB3/SPI3_SCK/I2S3_CK/TRACEWO/TIM2_CH2/SPI1_SCK)*_89") (pintype "bidirectional"))
      (node (ref "R21") (pin "1") (pinfunction "1_1") (pintype "passive"))
      (node (ref "XP1") (pin "13") (pinfunction "13_13") (pintype "passive"))
    )
    (net (code "142") (name "TMP75_ALERT") (class "Default")
      (node (ref "U2") (pin "3") (pinfunction "ALERT_3") (pintype "output"))
    )
    (net (code "143") (name "TMS") (class "Default")
      (node (ref "DD2") (pin "72") (pinfunction "JTMS/SWDIO(PA13)*_72") (pintype "bidirectional"))
      (node (ref "R78") (pin "1") (pinfunction "1_1") (pintype "passive"))
    )
    (net (code "144") (name "TO_GPS") (class "Default")
      (node (ref "DD2") (pin "68") (pinfunction "PA9(USART1_TX/TIM1_CH2)*_68") (pintype "bidirectional"))
      (node (ref "JP2") (pin "3") (pinfunction "3_3") (pintype "passive"))
    )
    (net (code "145") (name "TO_XBEE") (class "Default")
      (node (ref "DD2") (pin "25") (pinfunction "PA2(USART2_TX/ADC123_IN2/TIM5_CH3/TIM2_CH3)_25") (pintype "bidirectional"))
      (node (ref "JP1") (pin "3") (pinfunction "3_3") (pintype "passive"))
    )
    (net (code "146") (name "TRST") (class "Default")
      (node (ref "DD2") (pin "90") (pinfunction "NJTRST(PB4/SPI3_MISO/TIM3_CH1/SPI1_MISO)*_90") (pintype "bidirectional"))
      (node (ref "R17") (pin "1") (pinfunction "1_1") (pintype "passive"))
      (node (ref "XP1") (pin "3") (pinfunction "3_3") (pintype "passive"))
    )
    (net (code "147") (name "USB_DISCOVERY") (class "Default")
      (node (ref "DD2") (pin "3") (pinfunction "PE4(TRACED1/FSMC_A20)*_3") (pintype "bidirectional"))
      (node (ref "R62") (pin "1") (pinfunction "1_1") (pintype "passive"))
    )
    (net (code "148") (name "USB_DM") (class "Default")
      (node (ref "C16") (pin "2") (pinfunction "2_2") (pintype "passive"))
      (node (ref "DD2") (pin "70") (pinfunction "PA11(USBDM/CAN_RX/USART1_CTS/TIM1_CH4)*_70") (pintype "bidirectional"))
      (node (ref "R12") (pin "2") (pinfunction "2_2") (pintype "passive"))
    )
    (net (code "149") (name "USB_DP") (class "Default")
      (node (ref "C17") (pin "2") (pinfunction "2_2") (pintype "passive"))
      (node (ref "DD2") (pin "71") (pinfunction "PA12(USBDP/CAN_TX/USART1_RTS/TIM1_ETR)*_71") (pintype "bidirectional"))
      (node (ref "R10") (pin "1") (pinfunction "1_1") (pintype "passive"))
      (node (ref "R13") (pin "2") (pinfunction "2_2") (pintype "passive"))
    )
    (net (code "150") (name "VBAT") (class "Default")
      (node (ref "DD2") (pin "6") (pinfunction "V_BAT_6") (pintype "power_in"))
      (node (ref "JP6") (pin "2") (pinfunction "2_2") (pintype "passive"))
    )
    (net (code "151") (name "VDD_A") (class "Default")
      (node (ref "C14") (pin "A") (pinfunction "+_A") (pintype "passive"))
      (node (ref "C15") (pin "1") (pinfunction "1_1") (pintype "passive"))
      (node (ref "C22") (pin "1") (pinfunction "1_1") (pintype "passive"))
      (node (ref "DD2") (pin "22") (pinfunction "VDD_A_22") (pintype "power_in"))
      (node (ref "IC2") (pin "5") (pinfunction "V+_5") (pintype "power_in"))
      (node (ref "R79") (pin "1") (pinfunction "1_1") (pintype "passive"))
      (node (ref "R8") (pin "2") (pinfunction "2_2") (pintype "passive"))
    )
    (net (code "152") (name "VREF_MCU") (class "Default")
      (node (ref "DA6") (pin "5") (pinfunction "OUT_5") (pintype "power_in"))
      (node (ref "DD2") (pin "21") (pinfunction "VREF+_21") (pintype "power_in"))
      (node (ref "R53") (pin "2") (pinfunction "2_2") (pintype "passive"))
    )
    (net (code "153") (name "V_IN") (class "Default")
      (node (ref "F3") (pin "1") (pinfunction "1_1") (pintype "passive"))
      (node (ref "XP10") (pin "2") (pinfunction "2_2") (pintype "passive"))
      (node (ref "XP11") (pin "2") (pinfunction "2_2") (pintype "passive"))
      (node (ref "XP12") (pin "2") (pinfunction "2_2") (pintype "passive"))
      (node (ref "XP13") (pin "2") (pinfunction "2_2") (pintype "passive"))
      (node (ref "XP14") (pin "2") (pinfunction "2_2") (pintype "passive"))
      (node (ref "XP15") (pin "2") (pinfunction "2_2") (pintype "passive"))
      (node (ref "XP17") (pin "2") (pinfunction "2_2") (pintype "passive"))
      (node (ref "XP8") (pin "2") (pinfunction "2_2") (pintype "passive"))
      (node (ref "XP9") (pin "2") (pinfunction "2_2") (pintype "passive"))
    )
    (net (code "154") (name "XBEE_CTS") (class "Default")
      (node (ref "DD2") (pin "23") (pinfunction "PA0(WKUP/USART2_CTS/ADC123_IN0/TIM2_CH1_ETR/TIM5_CH1/TIM8_ETR)_23") (pintype "bidirectional"))
      (node (ref "JP1") (pin "4") (pinfunction "4_4") (pintype "passive"))
    )
    (net (code "155") (name "XBEE_RESET") (class "Default")
      (node (ref "DD2") (pin "1") (pinfunction "PE2(TRACECK/FSMC_A23)*_1") (pintype "bidirectional"))
      (node (ref "JP1") (pin "5") (pinfunction "5_5") (pintype "passive"))
    )
    (net (code "156") (name "XBEE_RTS") (class "Default")
      (node (ref "DD2") (pin "24") (pinfunction "PA1(USART2_RTS/ADC123_IN1/TIM5_CH2/TIM2_CH2)_24") (pintype "bidirectional"))
      (node (ref "JP1") (pin "6") (pinfunction "6_6") (pintype "passive"))
    )
    (net (code "157") (name "XBEE_SLEEP") (class "Default")
      (node (ref "DD2") (pin "98") (pinfunction "PE1(FSMC_NBL1)*_98") (pintype "bidirectional"))
      (node (ref "JP1") (pin "9") (pinfunction "9_9") (pintype "passive"))
    )
    (net (code "158") (name "unconnected-(DD2-PB5(I2C1_SMBA{slash}SPI3_MOSI{slash}I2S3_SD{slash}TIM3_CH2{slash}SPI1_MOSI)-Pad91)") (class "Default")
      (node (ref "DD2") (pin "91") (pinfunction "PB5(I2C1_SMBA/SPI3_MOSI/I2S3_SD/TIM3_CH2/SPI1_MOSI)_91") (pintype "bidirectional"))
    )
    (net (code "159") (name "unconnected-(DD2-PB9(TIM4_CH4{slash}SDIO_D5{slash}I2C1_SDA{slash}CAN_TX)*-Pad96)") (class "Default")
      (node (ref "DD2") (pin "96") (pinfunction "PB9(TIM4_CH4/SDIO_D5/I2C1_SDA/CAN_TX)*_96") (pintype "bidirectional"))
    )
    (net (code "160") (name "unconnected-(DD2-PB12(SPI2_NSS{slash}I2S2_WS{slash}I2C2_SMBA{slash}USART3_CK{slash}TIM1_BKIN)*-Pad51)") (class "Default")
      (node (ref "DD2") (pin "51") (pinfunction "PB12(SPI2_NSS/I2S2_WS/I2C2_SMBA/USART3_CK/TIM1_BKIN)*_51") (pintype "bidirectional"))
    )
    (net (code "161") (name "unconnected-(DD2-PB13(SPI2_SCK{slash}I2S2_SCK{slash}USART3_CTS{slash}TIM1_CH1N)*-Pad52)") (class "Default")
      (node (ref "DD2") (pin "52") (pinfunction "PB13(SPI2_SCK/I2S2_SCK/USART3_CTS/TIM1_CH1N)*_52") (pintype "bidirectional"))
    )
    (net (code "162") (name "unconnected-(DD2-PB14(SPI2_MISO{slash}USART3_RTS{slash}TIM1_CH2N)*-Pad53)") (class "Default")
      (node (ref "DD2") (pin "53") (pinfunction "PB14(SPI2_MISO/USART3_RTS/TIM1_CH2N)*_53") (pintype "bidirectional"))
    )
    (net (code "163") (name "unconnected-(DD2-PB15(SPI2_MOSI{slash}I2S2_SD{slash}TIM1_CH3N)*-Pad54)") (class "Default")
      (node (ref "DD2") (pin "54") (pinfunction "PB15(SPI2_MOSI/I2S2_SD/TIM1_CH3N)*_54") (pintype "bidirectional"))
    )
    (net (code "164") (name "unconnected-(DD2-PC6(I2S2_MCK{slash}TIM8_CH1{slash}SDIO_D6{slash}TIM3_CH1)*-Pad63)") (class "Default")
      (node (ref "DD2") (pin "63") (pinfunction "PC6(I2S2_MCK/TIM8_CH1/SDIO_D6/TIM3_CH1)*_63") (pintype "bidirectional"))
    )
    (net (code "165") (name "unconnected-(DD2-PC7(I2S3_MCK{slash}TIM8_CH2{slash}SDIO_D7{slash}TIM3_CH2)*-Pad64)") (class "Default")
      (node (ref "DD2") (pin "64") (pinfunction "PC7(I2S3_MCK/TIM8_CH2/SDIO_D7/TIM3_CH2)*_64") (pintype "bidirectional"))
    )
    (net (code "166") (name "unconnected-(DD2-PD0(OSC_IN{slash}FSMC_D2{slash}CAN_RX)*-Pad81)") (class "Default")
      (node (ref "DD2") (pin "81") (pinfunction "PD0(OSC_IN/FSMC_D2/CAN_RX)*_81") (pintype "bidirectional"))
    )
    (net (code "167") (name "unconnected-(DD2-PD1(OSC_OUT{slash}FSMC_D3{slash}CAN_TX)*-Pad82)") (class "Default")
      (node (ref "DD2") (pin "82") (pinfunction "PD1(OSC_OUT/FSMC_D3/CAN_TX)*_82") (pintype "bidirectional"))
    )
    (net (code "168") (name "unconnected-(DD2-PD3(FSMC_CLK{slash}USART2_CTS)*-Pad84)") (class "Default")
      (node (ref "DD2") (pin "84") (pinfunction "PD3(FSMC_CLK/USART2_CTS)*_84") (pintype "bidirectional"))
    )
    (net (code "169") (name "unconnected-(DD2-PD4(FSMC_NOE{slash}USART2_RTS)*-Pad85)") (class "Default")
      (node (ref "DD2") (pin "85") (pinfunction "PD4(FSMC_NOE/USART2_RTS)*_85") (pintype "bidirectional"))
    )
    (net (code "170") (name "unconnected-(DD2-PD5(FSMC_NWE{slash}USART2_TX)*-Pad86)") (class "Default")
      (node (ref "DD2") (pin "86") (pinfunction "PD5(FSMC_NWE/USART2_TX)*_86") (pintype "bidirectional"))
    )
    (net (code "171") (name "unconnected-(DD2-PD6(FSMC_NWAIT{slash}USART2_RX)*-Pad87)") (class "Default")
      (node (ref "DD2") (pin "87") (pinfunction "PD6(FSMC_NWAIT/USART2_RX)*_87") (pintype "bidirectional"))
    )
    (net (code "172") (name "unconnected-(DD2-PD7(FSMC_NE1{slash}FSMC_NCE2{slash}USART2_CK)*-Pad88)") (class "Default")
      (node (ref "DD2") (pin "88") (pinfunction "PD7(FSMC_NE1/FSMC_NCE2/USART2_CK)*_88") (pintype "bidirectional"))
    )
    (net (code "173") (name "unconnected-(DD2-PD8(FSMC_D13{slash}USART3_TX)*-Pad55)") (class "Default")
      (node (ref "DD2") (pin "55") (pinfunction "PD8(FSMC_D13/USART3_TX)*_55") (pintype "bidirectional"))
    )
    (net (code "174") (name "unconnected-(DD2-PD9(FSMC_D14{slash}USART3_RX)*-Pad56)") (class "Default")
      (node (ref "DD2") (pin "56") (pinfunction "PD9(FSMC_D14/USART3_RX)*_56") (pintype "bidirectional"))
    )
    (net (code "175") (name "unconnected-(DD2-PD10(FSMC_D15{slash}USART3_CK)*-Pad57)") (class "Default")
      (node (ref "DD2") (pin "57") (pinfunction "PD10(FSMC_D15/USART3_CK)*_57") (pintype "bidirectional"))
    )
    (net (code "176") (name "unconnected-(DD2-PD11(FSMC_A16{slash}USART3_CTS)*-Pad58)") (class "Default")
      (node (ref "DD2") (pin "58") (pinfunction "PD11(FSMC_A16/USART3_CTS)*_58") (pintype "bidirectional"))
    )
    (net (code "177") (name "unconnected-(DD2-PE12(FSMC_D9{slash}TIM1_CH3N)*-Pad43)") (class "Default")
      (node (ref "DD2") (pin "43") (pinfunction "PE12(FSMC_D9/TIM1_CH3N)*_43") (pintype "bidirectional"))
    )
    (net (code "178") (name "unconnected-(JP1-Pad7)") (class "Default")
      (node (ref "JP1") (pin "7") (pinfunction "7_7") (pintype "passive"))
    )
    (net (code "179") (name "unconnected-(JP1-Pad8)") (class "Default")
      (node (ref "JP1") (pin "8") (pinfunction "8_8") (pintype "passive"))
    )
    (net (code "180") (name "unconnected-(JP2-Pad5)") (class "Default")
      (node (ref "JP2") (pin "5") (pinfunction "5_5") (pintype "passive"))
    )
    (net (code "181") (name "unconnected-(JP2-Pad6)") (class "Default")
      (node (ref "JP2") (pin "6") (pinfunction "6_6") (pintype "passive"))
    )
    (net (code "182") (name "unconnected-(JP2-Pad8)") (class "Default")
      (node (ref "JP2") (pin "8") (pinfunction "8_8") (pintype "passive"))
    )
    (net (code "183") (name "unconnected-(JP2-Pad9)") (class "Default")
      (node (ref "JP2") (pin "9") (pinfunction "9_9") (pintype "passive"))
    )
    (net (code "184") (name "unconnected-(U44-NC-Pad5)") (class "Default")
      (node (ref "U44") (pin "5") (pinfunction "NC_5") (pintype "no_connect"))
    )
    (net (code "185") (name "unconnected-(XP17-Pad1)") (class "Default")
      (node (ref "XP17") (pin "1") (pinfunction "1_1") (pintype "passive"))
    )
  )
)
